# DIY_Keyboard_V1_2.net
KiCad netlist of a schematic drawn in EAGLE
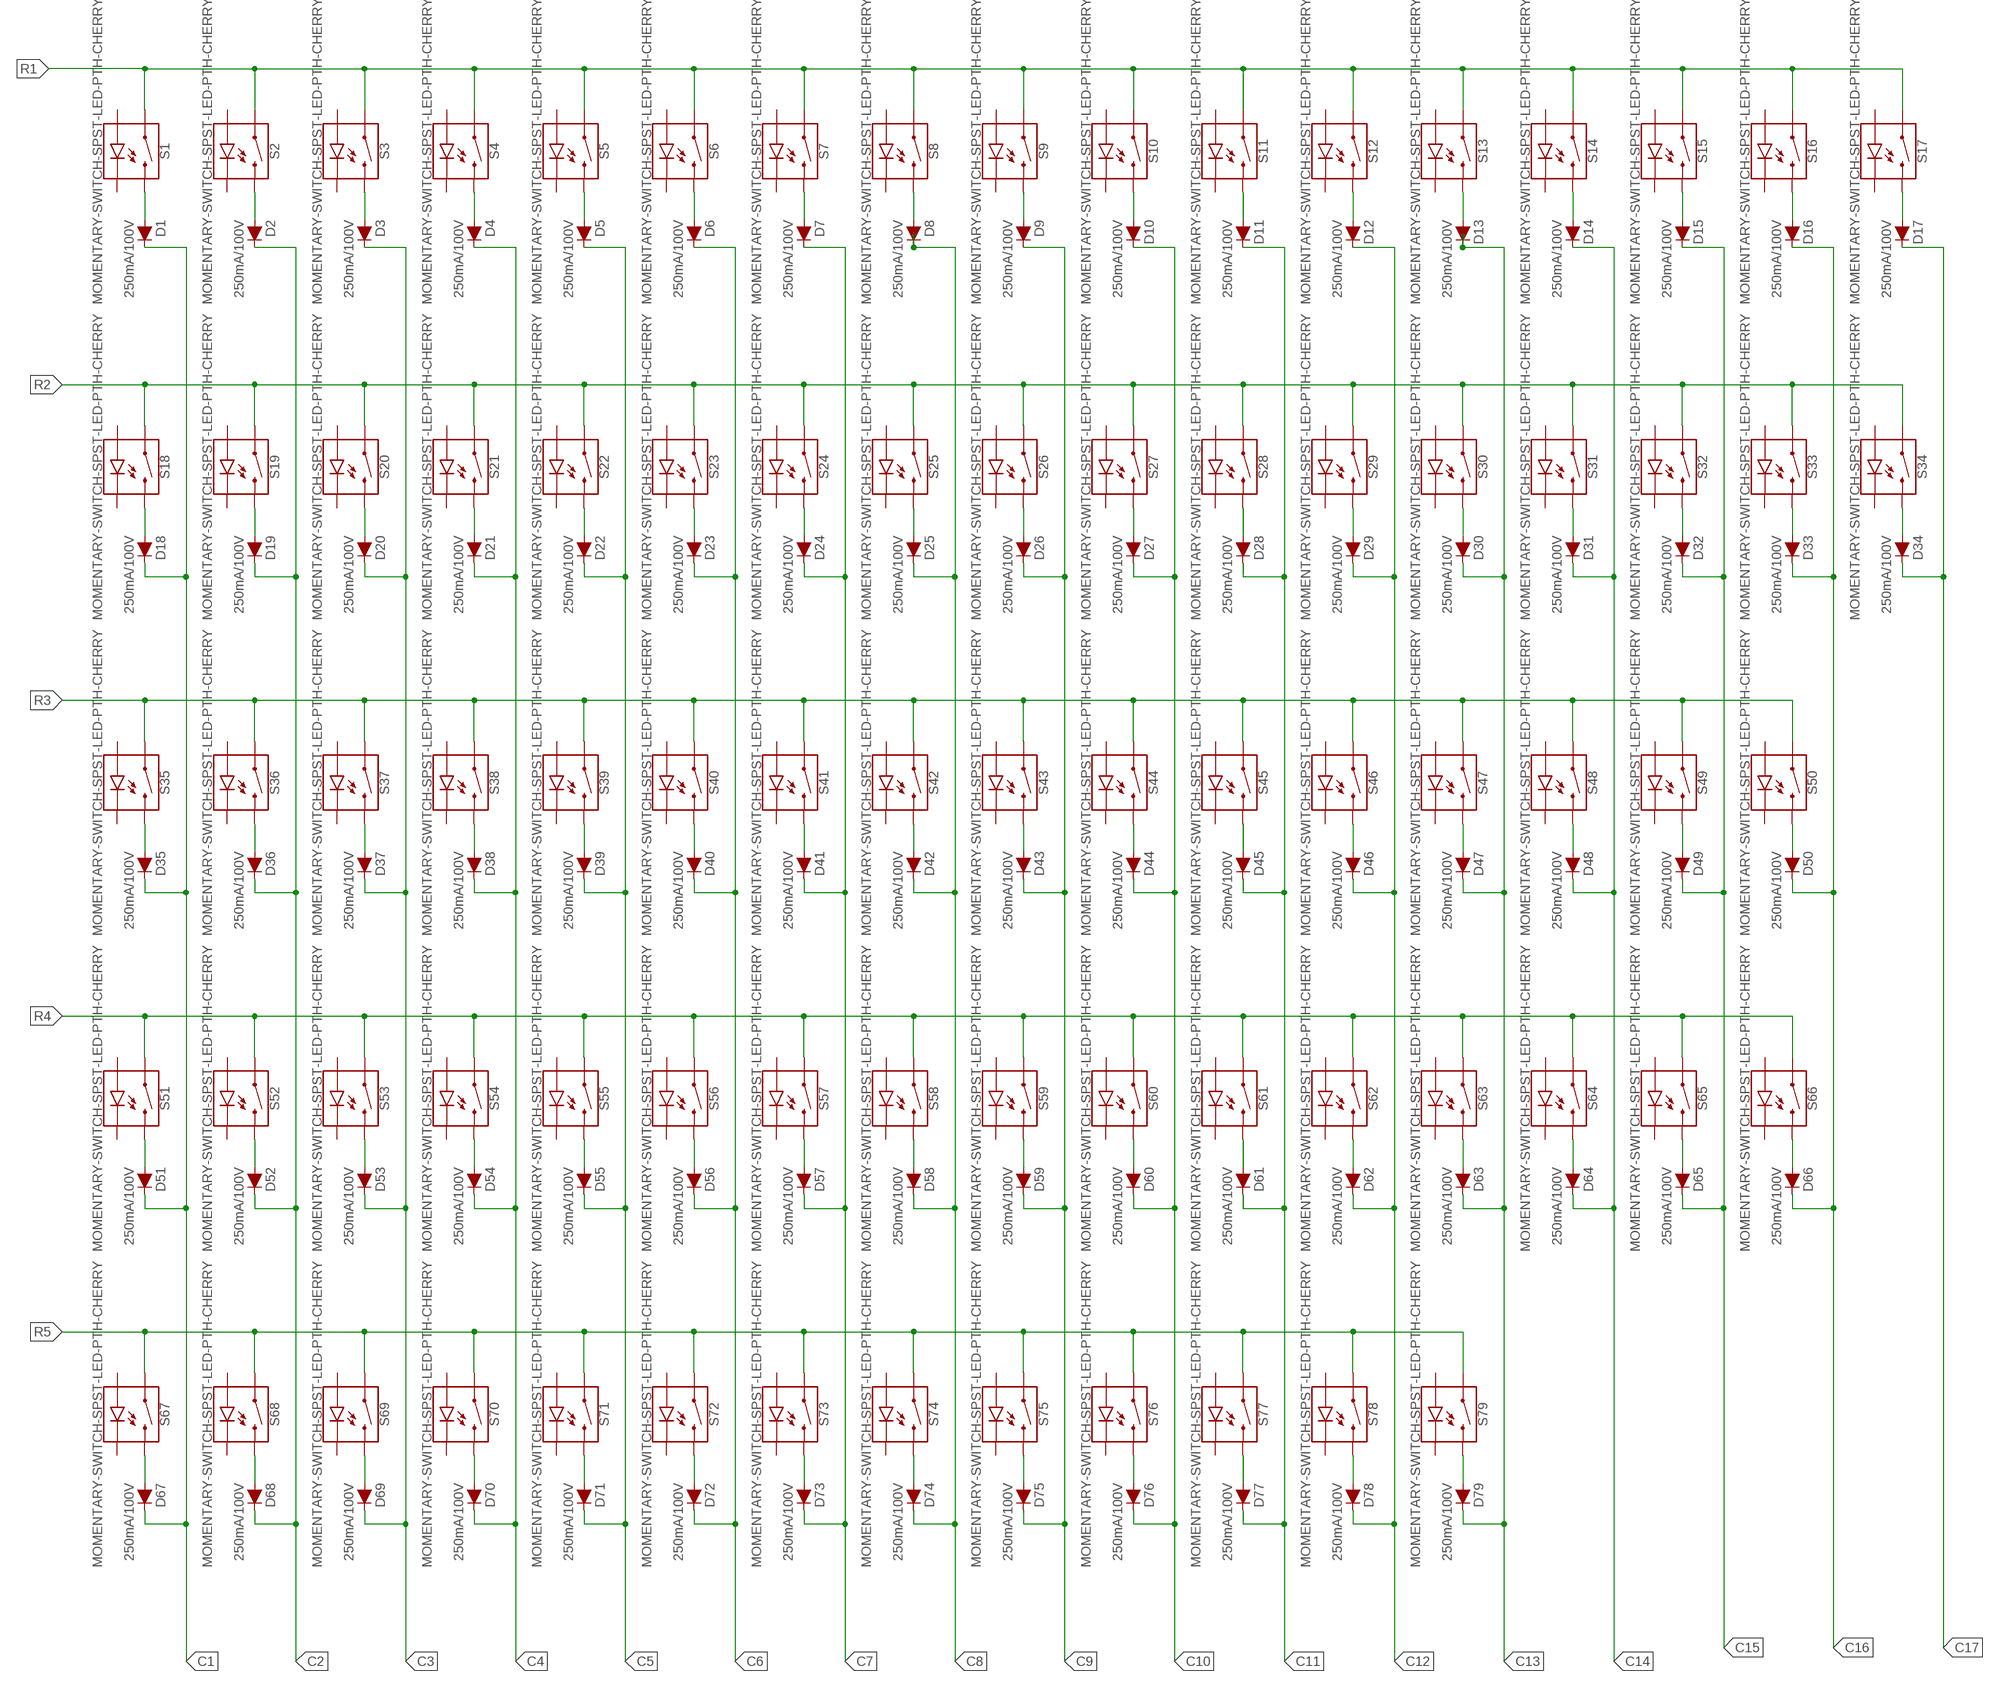
[diagram p0: schematic, sheet 1, part 1 of 2]
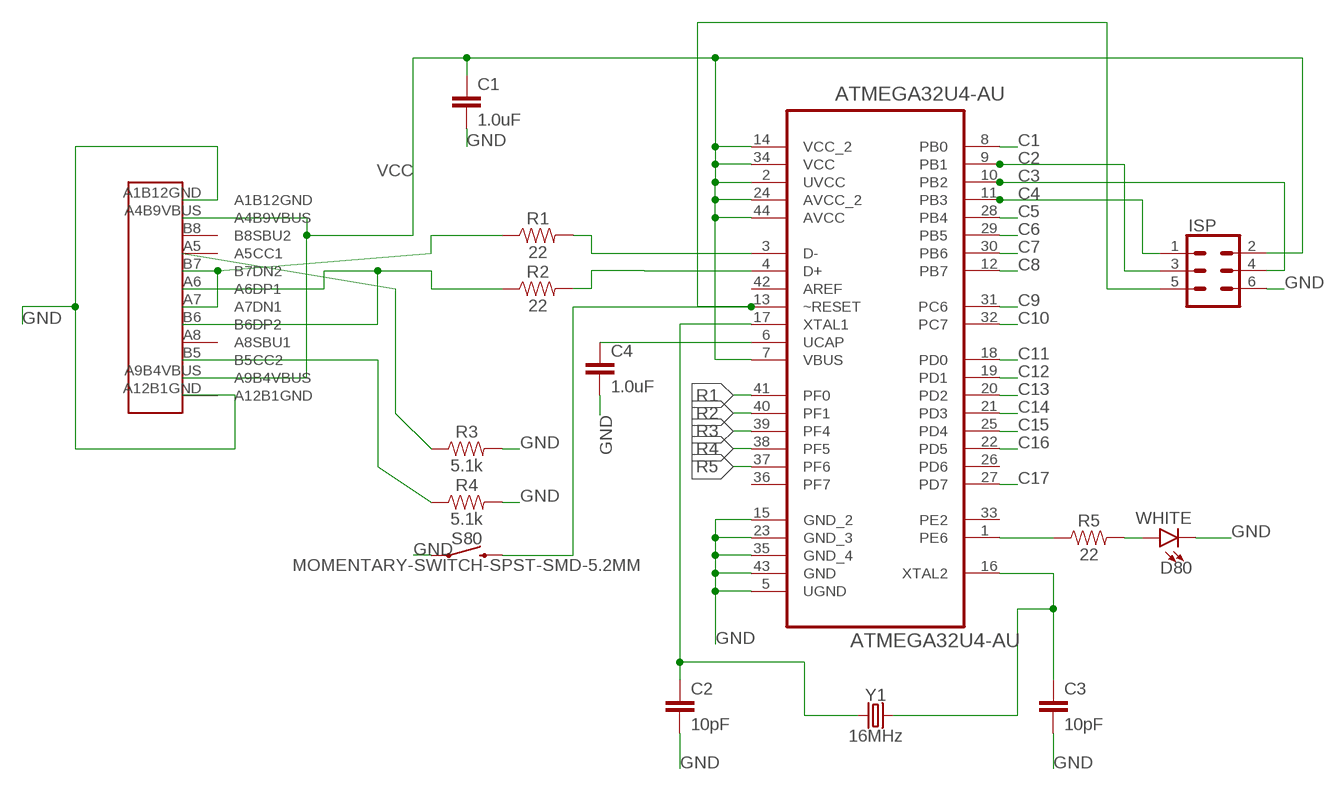
[diagram p1: schematic, sheet 1, part 2 of 2]

(export (version "E")
  (design (tool "Eeschema 10.0.6"))
  (components
    (comp (ref "ATMEGA32U4-AU")
      (value "ATMEGA32U4-AU")
      (footprint "eagle-import:QFP80P1200X1200X120-44N")
      (fields (field (name "MF") "Microchip"))
      (libsource (lib "eagle-import") (part "ATMEGA32U4-AU"))
    )
    (comp (ref "C1")
      (value "1.0uF")
      (footprint "eagle-import:0603")
      (libsource (lib "eagle-import") (part "1.0UF-0603-16V-10%"))
    )
    (comp (ref "C2")
      (value "10pF")
      (footprint "eagle-import:0603")
      (libsource (lib "eagle-import") (part "10PF-0603-50V-5%"))
    )
    (comp (ref "C3")
      (value "10pF")
      (footprint "eagle-import:0603")
      (libsource (lib "eagle-import") (part "10PF-0603-50V-5%"))
    )
    (comp (ref "C4")
      (value "1.0uF")
      (footprint "eagle-import:0603")
      (libsource (lib "eagle-import") (part "1.0UF-0603-16V-10%"))
    )
    (comp (ref "D1")
      (value "250mA/100V")
      (footprint "eagle-import:SOD-323")
      (libsource (lib "eagle-import") (part "DIODE-BAS16J"))
    )
    (comp (ref "D2")
      (value "250mA/100V")
      (footprint "eagle-import:SOD-323")
      (libsource (lib "eagle-import") (part "DIODE-BAS16J"))
    )
    (comp (ref "D3")
      (value "250mA/100V")
      (footprint "eagle-import:SOD-323")
      (libsource (lib "eagle-import") (part "DIODE-BAS16J"))
    )
    (comp (ref "D4")
      (value "250mA/100V")
      (footprint "eagle-import:SOD-323")
      (libsource (lib "eagle-import") (part "DIODE-BAS16J"))
    )
    (comp (ref "D5")
      (value "250mA/100V")
      (footprint "eagle-import:SOD-323")
      (libsource (lib "eagle-import") (part "DIODE-BAS16J"))
    )
    (comp (ref "D6")
      (value "250mA/100V")
      (footprint "eagle-import:SOD-323")
      (libsource (lib "eagle-import") (part "DIODE-BAS16J"))
    )
    (comp (ref "D7")
      (value "250mA/100V")
      (footprint "eagle-import:SOD-323")
      (libsource (lib "eagle-import") (part "DIODE-BAS16J"))
    )
    (comp (ref "D8")
      (value "250mA/100V")
      (footprint "eagle-import:SOD-323")
      (libsource (lib "eagle-import") (part "DIODE-BAS16J"))
    )
    (comp (ref "D9")
      (value "250mA/100V")
      (footprint "eagle-import:SOD-323")
      (libsource (lib "eagle-import") (part "DIODE-BAS16J"))
    )
    (comp (ref "D10")
      (value "250mA/100V")
      (footprint "eagle-import:SOD-323")
      (libsource (lib "eagle-import") (part "DIODE-BAS16J"))
    )
    (comp (ref "D11")
      (value "250mA/100V")
      (footprint "eagle-import:SOD-323")
      (libsource (lib "eagle-import") (part "DIODE-BAS16J"))
    )
    (comp (ref "D12")
      (value "250mA/100V")
      (footprint "eagle-import:SOD-323")
      (libsource (lib "eagle-import") (part "DIODE-BAS16J"))
    )
    (comp (ref "D13")
      (value "250mA/100V")
      (footprint "eagle-import:SOD-323")
      (libsource (lib "eagle-import") (part "DIODE-BAS16J"))
    )
    (comp (ref "D14")
      (value "250mA/100V")
      (footprint "eagle-import:SOD-323")
      (libsource (lib "eagle-import") (part "DIODE-BAS16J"))
    )
    (comp (ref "D15")
      (value "250mA/100V")
      (footprint "eagle-import:SOD-323")
      (libsource (lib "eagle-import") (part "DIODE-BAS16J"))
    )
    (comp (ref "D16")
      (value "250mA/100V")
      (footprint "eagle-import:SOD-323")
      (libsource (lib "eagle-import") (part "DIODE-BAS16J"))
    )
    (comp (ref "D17")
      (value "250mA/100V")
      (footprint "eagle-import:SOD-323")
      (libsource (lib "eagle-import") (part "DIODE-BAS16J"))
    )
    (comp (ref "D18")
      (value "250mA/100V")
      (footprint "eagle-import:SOD-323")
      (libsource (lib "eagle-import") (part "DIODE-BAS16J"))
    )
    (comp (ref "D19")
      (value "250mA/100V")
      (footprint "eagle-import:SOD-323")
      (libsource (lib "eagle-import") (part "DIODE-BAS16J"))
    )
    (comp (ref "D20")
      (value "250mA/100V")
      (footprint "eagle-import:SOD-323")
      (libsource (lib "eagle-import") (part "DIODE-BAS16J"))
    )
    (comp (ref "D21")
      (value "250mA/100V")
      (footprint "eagle-import:SOD-323")
      (libsource (lib "eagle-import") (part "DIODE-BAS16J"))
    )
    (comp (ref "D22")
      (value "250mA/100V")
      (footprint "eagle-import:SOD-323")
      (libsource (lib "eagle-import") (part "DIODE-BAS16J"))
    )
    (comp (ref "D23")
      (value "250mA/100V")
      (footprint "eagle-import:SOD-323")
      (libsource (lib "eagle-import") (part "DIODE-BAS16J"))
    )
    (comp (ref "D24")
      (value "250mA/100V")
      (footprint "eagle-import:SOD-323")
      (libsource (lib "eagle-import") (part "DIODE-BAS16J"))
    )
    (comp (ref "D25")
      (value "250mA/100V")
      (footprint "eagle-import:SOD-323")
      (libsource (lib "eagle-import") (part "DIODE-BAS16J"))
    )
    (comp (ref "D26")
      (value "250mA/100V")
      (footprint "eagle-import:SOD-323")
      (libsource (lib "eagle-import") (part "DIODE-BAS16J"))
    )
    (comp (ref "D27")
      (value "250mA/100V")
      (footprint "eagle-import:SOD-323")
      (libsource (lib "eagle-import") (part "DIODE-BAS16J"))
    )
    (comp (ref "D28")
      (value "250mA/100V")
      (footprint "eagle-import:SOD-323")
      (libsource (lib "eagle-import") (part "DIODE-BAS16J"))
    )
    (comp (ref "D29")
      (value "250mA/100V")
      (footprint "eagle-import:SOD-323")
      (libsource (lib "eagle-import") (part "DIODE-BAS16J"))
    )
    (comp (ref "D30")
      (value "250mA/100V")
      (footprint "eagle-import:SOD-323")
      (libsource (lib "eagle-import") (part "DIODE-BAS16J"))
    )
    (comp (ref "D31")
      (value "250mA/100V")
      (footprint "eagle-import:SOD-323")
      (libsource (lib "eagle-import") (part "DIODE-BAS16J"))
    )
    (comp (ref "D32")
      (value "250mA/100V")
      (footprint "eagle-import:SOD-323")
      (libsource (lib "eagle-import") (part "DIODE-BAS16J"))
    )
    (comp (ref "D33")
      (value "250mA/100V")
      (footprint "eagle-import:SOD-323")
      (libsource (lib "eagle-import") (part "DIODE-BAS16J"))
    )
    (comp (ref "D34")
      (value "250mA/100V")
      (footprint "eagle-import:SOD-323")
      (libsource (lib "eagle-import") (part "DIODE-BAS16J"))
    )
    (comp (ref "D35")
      (value "250mA/100V")
      (footprint "eagle-import:SOD-323")
      (libsource (lib "eagle-import") (part "DIODE-BAS16J"))
    )
    (comp (ref "D36")
      (value "250mA/100V")
      (footprint "eagle-import:SOD-323")
      (libsource (lib "eagle-import") (part "DIODE-BAS16J"))
    )
    (comp (ref "D37")
      (value "250mA/100V")
      (footprint "eagle-import:SOD-323")
      (libsource (lib "eagle-import") (part "DIODE-BAS16J"))
    )
    (comp (ref "D38")
      (value "250mA/100V")
      (footprint "eagle-import:SOD-323")
      (libsource (lib "eagle-import") (part "DIODE-BAS16J"))
    )
    (comp (ref "D39")
      (value "250mA/100V")
      (footprint "eagle-import:SOD-323")
      (libsource (lib "eagle-import") (part "DIODE-BAS16J"))
    )
    (comp (ref "D40")
      (value "250mA/100V")
      (footprint "eagle-import:SOD-323")
      (libsource (lib "eagle-import") (part "DIODE-BAS16J"))
    )
    (comp (ref "D41")
      (value "250mA/100V")
      (footprint "eagle-import:SOD-323")
      (libsource (lib "eagle-import") (part "DIODE-BAS16J"))
    )
    (comp (ref "D42")
      (value "250mA/100V")
      (footprint "eagle-import:SOD-323")
      (libsource (lib "eagle-import") (part "DIODE-BAS16J"))
    )
    (comp (ref "D43")
      (value "250mA/100V")
      (footprint "eagle-import:SOD-323")
      (libsource (lib "eagle-import") (part "DIODE-BAS16J"))
    )
    (comp (ref "D44")
      (value "250mA/100V")
      (footprint "eagle-import:SOD-323")
      (libsource (lib "eagle-import") (part "DIODE-BAS16J"))
    )
    (comp (ref "D45")
      (value "250mA/100V")
      (footprint "eagle-import:SOD-323")
      (libsource (lib "eagle-import") (part "DIODE-BAS16J"))
    )
    (comp (ref "D46")
      (value "250mA/100V")
      (footprint "eagle-import:SOD-323")
      (libsource (lib "eagle-import") (part "DIODE-BAS16J"))
    )
    (comp (ref "D47")
      (value "250mA/100V")
      (footprint "eagle-import:SOD-323")
      (libsource (lib "eagle-import") (part "DIODE-BAS16J"))
    )
    (comp (ref "D48")
      (value "250mA/100V")
      (footprint "eagle-import:SOD-323")
      (libsource (lib "eagle-import") (part "DIODE-BAS16J"))
    )
    (comp (ref "D49")
      (value "250mA/100V")
      (footprint "eagle-import:SOD-323")
      (libsource (lib "eagle-import") (part "DIODE-BAS16J"))
    )
    (comp (ref "D50")
      (value "250mA/100V")
      (footprint "eagle-import:SOD-323")
      (libsource (lib "eagle-import") (part "DIODE-BAS16J"))
    )
    (comp (ref "D51")
      (value "250mA/100V")
      (footprint "eagle-import:SOD-323")
      (libsource (lib "eagle-import") (part "DIODE-BAS16J"))
    )
    (comp (ref "D52")
      (value "250mA/100V")
      (footprint "eagle-import:SOD-323")
      (libsource (lib "eagle-import") (part "DIODE-BAS16J"))
    )
    (comp (ref "D53")
      (value "250mA/100V")
      (footprint "eagle-import:SOD-323")
      (libsource (lib "eagle-import") (part "DIODE-BAS16J"))
    )
    (comp (ref "D54")
      (value "250mA/100V")
      (footprint "eagle-import:SOD-323")
      (libsource (lib "eagle-import") (part "DIODE-BAS16J"))
    )
    (comp (ref "D55")
      (value "250mA/100V")
      (footprint "eagle-import:SOD-323")
      (libsource (lib "eagle-import") (part "DIODE-BAS16J"))
    )
    (comp (ref "D56")
      (value "250mA/100V")
      (footprint "eagle-import:SOD-323")
      (libsource (lib "eagle-import") (part "DIODE-BAS16J"))
    )
    (comp (ref "D57")
      (value "250mA/100V")
      (footprint "eagle-import:SOD-323")
      (libsource (lib "eagle-import") (part "DIODE-BAS16J"))
    )
    (comp (ref "D58")
      (value "250mA/100V")
      (footprint "eagle-import:SOD-323")
      (libsource (lib "eagle-import") (part "DIODE-BAS16J"))
    )
    (comp (ref "D59")
      (value "250mA/100V")
      (footprint "eagle-import:SOD-323")
      (libsource (lib "eagle-import") (part "DIODE-BAS16J"))
    )
    (comp (ref "D60")
      (value "250mA/100V")
      (footprint "eagle-import:SOD-323")
      (libsource (lib "eagle-import") (part "DIODE-BAS16J"))
    )
    (comp (ref "D61")
      (value "250mA/100V")
      (footprint "eagle-import:SOD-323")
      (libsource (lib "eagle-import") (part "DIODE-BAS16J"))
    )
    (comp (ref "D62")
      (value "250mA/100V")
      (footprint "eagle-import:SOD-323")
      (libsource (lib "eagle-import") (part "DIODE-BAS16J"))
    )
    (comp (ref "D63")
      (value "250mA/100V")
      (footprint "eagle-import:SOD-323")
      (libsource (lib "eagle-import") (part "DIODE-BAS16J"))
    )
    (comp (ref "D64")
      (value "250mA/100V")
      (footprint "eagle-import:SOD-323")
      (libsource (lib "eagle-import") (part "DIODE-BAS16J"))
    )
    (comp (ref "D65")
      (value "250mA/100V")
      (footprint "eagle-import:SOD-323")
      (libsource (lib "eagle-import") (part "DIODE-BAS16J"))
    )
    (comp (ref "D66")
      (value "250mA/100V")
      (footprint "eagle-import:SOD-323")
      (libsource (lib "eagle-import") (part "DIODE-BAS16J"))
    )
    (comp (ref "D67")
      (value "250mA/100V")
      (footprint "eagle-import:SOD-323")
      (libsource (lib "eagle-import") (part "DIODE-BAS16J"))
    )
    (comp (ref "D68")
      (value "250mA/100V")
      (footprint "eagle-import:SOD-323")
      (libsource (lib "eagle-import") (part "DIODE-BAS16J"))
    )
    (comp (ref "D69")
      (value "250mA/100V")
      (footprint "eagle-import:SOD-323")
      (libsource (lib "eagle-import") (part "DIODE-BAS16J"))
    )
    (comp (ref "D70")
      (value "250mA/100V")
      (footprint "eagle-import:SOD-323")
      (libsource (lib "eagle-import") (part "DIODE-BAS16J"))
    )
    (comp (ref "D71")
      (value "250mA/100V")
      (footprint "eagle-import:SOD-323")
      (libsource (lib "eagle-import") (part "DIODE-BAS16J"))
    )
    (comp (ref "D72")
      (value "250mA/100V")
      (footprint "eagle-import:SOD-323")
      (libsource (lib "eagle-import") (part "DIODE-BAS16J"))
    )
    (comp (ref "D73")
      (value "250mA/100V")
      (footprint "eagle-import:SOD-323")
      (libsource (lib "eagle-import") (part "DIODE-BAS16J"))
    )
    (comp (ref "D74")
      (value "250mA/100V")
      (footprint "eagle-import:SOD-323")
      (libsource (lib "eagle-import") (part "DIODE-BAS16J"))
    )
    (comp (ref "D75")
      (value "250mA/100V")
      (footprint "eagle-import:SOD-323")
      (libsource (lib "eagle-import") (part "DIODE-BAS16J"))
    )
    (comp (ref "D76")
      (value "250mA/100V")
      (footprint "eagle-import:SOD-323")
      (libsource (lib "eagle-import") (part "DIODE-BAS16J"))
    )
    (comp (ref "D77")
      (value "250mA/100V")
      (footprint "eagle-import:SOD-323")
      (libsource (lib "eagle-import") (part "DIODE-BAS16J"))
    )
    (comp (ref "D78")
      (value "250mA/100V")
      (footprint "eagle-import:SOD-323")
      (libsource (lib "eagle-import") (part "DIODE-BAS16J"))
    )
    (comp (ref "D79")
      (value "250mA/100V")
      (footprint "eagle-import:SOD-323")
      (libsource (lib "eagle-import") (part "DIODE-BAS16J"))
    )
    (comp (ref "D80")
      (value "WHITE")
      (footprint "eagle-import:LED-0603")
      (libsource (lib "eagle-import") (part "LED-WHITE0603"))
    )
    (comp (ref "ISP")
      (value "CONN_03X2FEMALE")
      (footprint "eagle-import:2X3")
      (libsource (lib "eagle-import") (part "CONN_03X2FEMALE"))
    )
    (comp (ref "R1")
      (value "22")
      (footprint "eagle-import:0603")
      (libsource (lib "eagle-import") (part "22OHM-0603-1/10W-1%"))
    )
    (comp (ref "R2")
      (value "22")
      (footprint "eagle-import:0603")
      (libsource (lib "eagle-import") (part "22OHM-0603-1/10W-1%"))
    )
    (comp (ref "R3")
      (value "5.1k")
      (footprint "eagle-import:0603")
      (libsource (lib "eagle-import") (part "56KOHM"))
    )
    (comp (ref "R4")
      (value "5.1k")
      (footprint "eagle-import:0603")
      (libsource (lib "eagle-import") (part "56KOHM"))
    )
    (comp (ref "R5")
      (value "22")
      (footprint "eagle-import:0603")
      (libsource (lib "eagle-import") (part "22OHM-0603-1/10W-1%"))
    )
    (comp (ref "S1")
      (value "MOMENTARY-SWITCH-SPST-LED-PTH-CHERRY")
      (footprint "eagle-import:CHERRY-MX-LED")
      (libsource (lib "eagle-import") (part "MOMENTARY-SWITCH-SPST-LED-PTH-CHERRY"))
    )
    (comp (ref "S2")
      (value "MOMENTARY-SWITCH-SPST-LED-PTH-CHERRY")
      (footprint "eagle-import:CHERRY-MX-LED")
      (libsource (lib "eagle-import") (part "MOMENTARY-SWITCH-SPST-LED-PTH-CHERRY"))
    )
    (comp (ref "S3")
      (value "MOMENTARY-SWITCH-SPST-LED-PTH-CHERRY")
      (footprint "eagle-import:CHERRY-MX-LED")
      (libsource (lib "eagle-import") (part "MOMENTARY-SWITCH-SPST-LED-PTH-CHERRY"))
    )
    (comp (ref "S4")
      (value "MOMENTARY-SWITCH-SPST-LED-PTH-CHERRY")
      (footprint "eagle-import:CHERRY-MX-LED")
      (libsource (lib "eagle-import") (part "MOMENTARY-SWITCH-SPST-LED-PTH-CHERRY"))
    )
    (comp (ref "S5")
      (value "MOMENTARY-SWITCH-SPST-LED-PTH-CHERRY")
      (footprint "eagle-import:CHERRY-MX-LED")
      (libsource (lib "eagle-import") (part "MOMENTARY-SWITCH-SPST-LED-PTH-CHERRY"))
    )
    (comp (ref "S6")
      (value "MOMENTARY-SWITCH-SPST-LED-PTH-CHERRY")
      (footprint "eagle-import:CHERRY-MX-LED")
      (libsource (lib "eagle-import") (part "MOMENTARY-SWITCH-SPST-LED-PTH-CHERRY"))
    )
    (comp (ref "S7")
      (value "MOMENTARY-SWITCH-SPST-LED-PTH-CHERRY")
      (footprint "eagle-import:CHERRY-MX-LED")
      (libsource (lib "eagle-import") (part "MOMENTARY-SWITCH-SPST-LED-PTH-CHERRY"))
    )
    (comp (ref "S8")
      (value "MOMENTARY-SWITCH-SPST-LED-PTH-CHERRY")
      (footprint "eagle-import:CHERRY-MX-LED")
      (libsource (lib "eagle-import") (part "MOMENTARY-SWITCH-SPST-LED-PTH-CHERRY"))
    )
    (comp (ref "S9")
      (value "MOMENTARY-SWITCH-SPST-LED-PTH-CHERRY")
      (footprint "eagle-import:CHERRY-MX-LED")
      (libsource (lib "eagle-import") (part "MOMENTARY-SWITCH-SPST-LED-PTH-CHERRY"))
    )
    (comp (ref "S10")
      (value "MOMENTARY-SWITCH-SPST-LED-PTH-CHERRY")
      (footprint "eagle-import:CHERRY-MX-LED")
      (libsource (lib "eagle-import") (part "MOMENTARY-SWITCH-SPST-LED-PTH-CHERRY"))
    )
    (comp (ref "S11")
      (value "MOMENTARY-SWITCH-SPST-LED-PTH-CHERRY")
      (footprint "eagle-import:CHERRY-MX-LED")
      (libsource (lib "eagle-import") (part "MOMENTARY-SWITCH-SPST-LED-PTH-CHERRY"))
    )
    (comp (ref "S12")
      (value "MOMENTARY-SWITCH-SPST-LED-PTH-CHERRY")
      (footprint "eagle-import:CHERRY-MX-LED")
      (libsource (lib "eagle-import") (part "MOMENTARY-SWITCH-SPST-LED-PTH-CHERRY"))
    )
    (comp (ref "S13")
      (value "MOMENTARY-SWITCH-SPST-LED-PTH-CHERRY")
      (footprint "eagle-import:CHERRY-MX-LED")
      (libsource (lib "eagle-import") (part "MOMENTARY-SWITCH-SPST-LED-PTH-CHERRY"))
    )
    (comp (ref "S14")
      (value "MOMENTARY-SWITCH-SPST-LED-PTH-CHERRY")
      (footprint "eagle-import:CHERRY-MX-LED")
      (libsource (lib "eagle-import") (part "MOMENTARY-SWITCH-SPST-LED-PTH-CHERRY"))
    )
    (comp (ref "S15")
      (value "MOMENTARY-SWITCH-SPST-LED-PTH-CHERRY")
      (footprint "eagle-import:CHERRY-MX-LED")
      (libsource (lib "eagle-import") (part "MOMENTARY-SWITCH-SPST-LED-PTH-CHERRY"))
    )
    (comp (ref "S16")
      (value "MOMENTARY-SWITCH-SPST-LED-PTH-CHERRY")
      (footprint "eagle-import:CHERRY-MX-LED")
      (libsource (lib "eagle-import") (part "MOMENTARY-SWITCH-SPST-LED-PTH-CHERRY"))
    )
    (comp (ref "S17")
      (value "MOMENTARY-SWITCH-SPST-LED-PTH-CHERRY")
      (footprint "eagle-import:CHERRY-MX-LED")
      (libsource (lib "eagle-import") (part "MOMENTARY-SWITCH-SPST-LED-PTH-CHERRY"))
    )
    (comp (ref "S18")
      (value "MOMENTARY-SWITCH-SPST-LED-PTH-CHERRY")
      (footprint "eagle-import:CHERRY-MX-LED")
      (libsource (lib "eagle-import") (part "MOMENTARY-SWITCH-SPST-LED-PTH-CHERRY"))
    )
    (comp (ref "S19")
      (value "MOMENTARY-SWITCH-SPST-LED-PTH-CHERRY")
      (footprint "eagle-import:CHERRY-MX-LED")
      (libsource (lib "eagle-import") (part "MOMENTARY-SWITCH-SPST-LED-PTH-CHERRY"))
    )
    (comp (ref "S20")
      (value "MOMENTARY-SWITCH-SPST-LED-PTH-CHERRY")
      (footprint "eagle-import:CHERRY-MX-LED")
      (libsource (lib "eagle-import") (part "MOMENTARY-SWITCH-SPST-LED-PTH-CHERRY"))
    )
    (comp (ref "S21")
      (value "MOMENTARY-SWITCH-SPST-LED-PTH-CHERRY")
      (footprint "eagle-import:CHERRY-MX-LED")
      (libsource (lib "eagle-import") (part "MOMENTARY-SWITCH-SPST-LED-PTH-CHERRY"))
    )
    (comp (ref "S22")
      (value "MOMENTARY-SWITCH-SPST-LED-PTH-CHERRY")
      (footprint "eagle-import:CHERRY-MX-LED")
      (libsource (lib "eagle-import") (part "MOMENTARY-SWITCH-SPST-LED-PTH-CHERRY"))
    )
    (comp (ref "S23")
      (value "MOMENTARY-SWITCH-SPST-LED-PTH-CHERRY")
      (footprint "eagle-import:CHERRY-MX-LED")
      (libsource (lib "eagle-import") (part "MOMENTARY-SWITCH-SPST-LED-PTH-CHERRY"))
    )
    (comp (ref "S24")
      (value "MOMENTARY-SWITCH-SPST-LED-PTH-CHERRY")
      (footprint "eagle-import:CHERRY-MX-LED")
      (libsource (lib "eagle-import") (part "MOMENTARY-SWITCH-SPST-LED-PTH-CHERRY"))
    )
    (comp (ref "S25")
      (value "MOMENTARY-SWITCH-SPST-LED-PTH-CHERRY")
      (footprint "eagle-import:CHERRY-MX-LED")
      (libsource (lib "eagle-import") (part "MOMENTARY-SWITCH-SPST-LED-PTH-CHERRY"))
    )
    (comp (ref "S26")
      (value "MOMENTARY-SWITCH-SPST-LED-PTH-CHERRY")
      (footprint "eagle-import:CHERRY-MX-LED")
      (libsource (lib "eagle-import") (part "MOMENTARY-SWITCH-SPST-LED-PTH-CHERRY"))
    )
    (comp (ref "S27")
      (value "MOMENTARY-SWITCH-SPST-LED-PTH-CHERRY")
      (footprint "eagle-import:CHERRY-MX-LED")
      (libsource (lib "eagle-import") (part "MOMENTARY-SWITCH-SPST-LED-PTH-CHERRY"))
    )
    (comp (ref "S28")
      (value "MOMENTARY-SWITCH-SPST-LED-PTH-CHERRY")
      (footprint "eagle-import:CHERRY-MX-LED")
      (libsource (lib "eagle-import") (part "MOMENTARY-SWITCH-SPST-LED-PTH-CHERRY"))
    )
    (comp (ref "S29")
      (value "MOMENTARY-SWITCH-SPST-LED-PTH-CHERRY")
      (footprint "eagle-import:CHERRY-MX-LED")
      (libsource (lib "eagle-import") (part "MOMENTARY-SWITCH-SPST-LED-PTH-CHERRY"))
    )
    (comp (ref "S30")
      (value "MOMENTARY-SWITCH-SPST-LED-PTH-CHERRY")
      (footprint "eagle-import:CHERRY-MX-LED")
      (libsource (lib "eagle-import") (part "MOMENTARY-SWITCH-SPST-LED-PTH-CHERRY"))
    )
    (comp (ref "S31")
      (value "MOMENTARY-SWITCH-SPST-LED-PTH-CHERRY")
      (footprint "eagle-import:CHERRY-MX-LED")
      (libsource (lib "eagle-import") (part "MOMENTARY-SWITCH-SPST-LED-PTH-CHERRY"))
    )
    (comp (ref "S32")
      (value "MOMENTARY-SWITCH-SPST-LED-PTH-CHERRY")
      (footprint "eagle-import:CHERRY-MX-LED")
      (libsource (lib "eagle-import") (part "MOMENTARY-SWITCH-SPST-LED-PTH-CHERRY"))
    )
    (comp (ref "S33")
      (value "MOMENTARY-SWITCH-SPST-LED-PTH-CHERRY")
      (footprint "eagle-import:CHERRY-MX-LED")
      (libsource (lib "eagle-import") (part "MOMENTARY-SWITCH-SPST-LED-PTH-CHERRY"))
    )
    (comp (ref "S34")
      (value "MOMENTARY-SWITCH-SPST-LED-PTH-CHERRY")
      (footprint "eagle-import:CHERRY-MX-LED")
      (libsource (lib "eagle-import") (part "MOMENTARY-SWITCH-SPST-LED-PTH-CHERRY"))
    )
    (comp (ref "S35")
      (value "MOMENTARY-SWITCH-SPST-LED-PTH-CHERRY")
      (footprint "eagle-import:CHERRY-MX-LED")
      (libsource (lib "eagle-import") (part "MOMENTARY-SWITCH-SPST-LED-PTH-CHERRY"))
    )
    (comp (ref "S36")
      (value "MOMENTARY-SWITCH-SPST-LED-PTH-CHERRY")
      (footprint "eagle-import:CHERRY-MX-LED")
      (libsource (lib "eagle-import") (part "MOMENTARY-SWITCH-SPST-LED-PTH-CHERRY"))
    )
    (comp (ref "S37")
      (value "MOMENTARY-SWITCH-SPST-LED-PTH-CHERRY")
      (footprint "eagle-import:CHERRY-MX-LED")
      (libsource (lib "eagle-import") (part "MOMENTARY-SWITCH-SPST-LED-PTH-CHERRY"))
    )
    (comp (ref "S38")
      (value "MOMENTARY-SWITCH-SPST-LED-PTH-CHERRY")
      (footprint "eagle-import:CHERRY-MX-LED")
      (libsource (lib "eagle-import") (part "MOMENTARY-SWITCH-SPST-LED-PTH-CHERRY"))
    )
    (comp (ref "S39")
      (value "MOMENTARY-SWITCH-SPST-LED-PTH-CHERRY")
      (footprint "eagle-import:CHERRY-MX-LED")
      (libsource (lib "eagle-import") (part "MOMENTARY-SWITCH-SPST-LED-PTH-CHERRY"))
    )
    (comp (ref "S40")
      (value "MOMENTARY-SWITCH-SPST-LED-PTH-CHERRY")
      (footprint "eagle-import:CHERRY-MX-LED")
      (libsource (lib "eagle-import") (part "MOMENTARY-SWITCH-SPST-LED-PTH-CHERRY"))
    )
    (comp (ref "S41")
      (value "MOMENTARY-SWITCH-SPST-LED-PTH-CHERRY")
      (footprint "eagle-import:CHERRY-MX-LED")
      (libsource (lib "eagle-import") (part "MOMENTARY-SWITCH-SPST-LED-PTH-CHERRY"))
    )
    (comp (ref "S42")
      (value "MOMENTARY-SWITCH-SPST-LED-PTH-CHERRY")
      (footprint "eagle-import:CHERRY-MX-LED")
      (libsource (lib "eagle-import") (part "MOMENTARY-SWITCH-SPST-LED-PTH-CHERRY"))
    )
    (comp (ref "S43")
      (value "MOMENTARY-SWITCH-SPST-LED-PTH-CHERRY")
      (footprint "eagle-import:CHERRY-MX-LED")
      (libsource (lib "eagle-import") (part "MOMENTARY-SWITCH-SPST-LED-PTH-CHERRY"))
    )
    (comp (ref "S44")
      (value "MOMENTARY-SWITCH-SPST-LED-PTH-CHERRY")
      (footprint "eagle-import:CHERRY-MX-LED")
      (libsource (lib "eagle-import") (part "MOMENTARY-SWITCH-SPST-LED-PTH-CHERRY"))
    )
    (comp (ref "S45")
      (value "MOMENTARY-SWITCH-SPST-LED-PTH-CHERRY")
      (footprint "eagle-import:CHERRY-MX-LED")
      (libsource (lib "eagle-import") (part "MOMENTARY-SWITCH-SPST-LED-PTH-CHERRY"))
    )
    (comp (ref "S46")
      (value "MOMENTARY-SWITCH-SPST-LED-PTH-CHERRY")
      (footprint "eagle-import:CHERRY-MX-LED")
      (libsource (lib "eagle-import") (part "MOMENTARY-SWITCH-SPST-LED-PTH-CHERRY"))
    )
    (comp (ref "S47")
      (value "MOMENTARY-SWITCH-SPST-LED-PTH-CHERRY")
      (footprint "eagle-import:CHERRY-MX-LED")
      (libsource (lib "eagle-import") (part "MOMENTARY-SWITCH-SPST-LED-PTH-CHERRY"))
    )
    (comp (ref "S48")
      (value "MOMENTARY-SWITCH-SPST-LED-PTH-CHERRY")
      (footprint "eagle-import:CHERRY-MX-LED")
      (libsource (lib "eagle-import") (part "MOMENTARY-SWITCH-SPST-LED-PTH-CHERRY"))
    )
    (comp (ref "S49")
      (value "MOMENTARY-SWITCH-SPST-LED-PTH-CHERRY")
      (footprint "eagle-import:CHERRY-MX-LED")
      (libsource (lib "eagle-import") (part "MOMENTARY-SWITCH-SPST-LED-PTH-CHERRY"))
    )
    (comp (ref "S50")
      (value "MOMENTARY-SWITCH-SPST-LED-PTH-CHERRY")
      (footprint "eagle-import:CHERRY-MX-LED")
      (libsource (lib "eagle-import") (part "MOMENTARY-SWITCH-SPST-LED-PTH-CHERRY"))
    )
    (comp (ref "S51")
      (value "MOMENTARY-SWITCH-SPST-LED-PTH-CHERRY")
      (footprint "eagle-import:CHERRY-MX-LED")
      (libsource (lib "eagle-import") (part "MOMENTARY-SWITCH-SPST-LED-PTH-CHERRY"))
    )
    (comp (ref "S52")
      (value "MOMENTARY-SWITCH-SPST-LED-PTH-CHERRY")
      (footprint "eagle-import:CHERRY-MX-LED")
      (libsource (lib "eagle-import") (part "MOMENTARY-SWITCH-SPST-LED-PTH-CHERRY"))
    )
    (comp (ref "S53")
      (value "MOMENTARY-SWITCH-SPST-LED-PTH-CHERRY")
      (footprint "eagle-import:CHERRY-MX-LED")
      (libsource (lib "eagle-import") (part "MOMENTARY-SWITCH-SPST-LED-PTH-CHERRY"))
    )
    (comp (ref "S54")
      (value "MOMENTARY-SWITCH-SPST-LED-PTH-CHERRY")
      (footprint "eagle-import:CHERRY-MX-LED")
      (libsource (lib "eagle-import") (part "MOMENTARY-SWITCH-SPST-LED-PTH-CHERRY"))
    )
    (comp (ref "S55")
      (value "MOMENTARY-SWITCH-SPST-LED-PTH-CHERRY")
      (footprint "eagle-import:CHERRY-MX-LED")
      (libsource (lib "eagle-import") (part "MOMENTARY-SWITCH-SPST-LED-PTH-CHERRY"))
    )
    (comp (ref "S56")
      (value "MOMENTARY-SWITCH-SPST-LED-PTH-CHERRY")
      (footprint "eagle-import:CHERRY-MX-LED")
      (libsource (lib "eagle-import") (part "MOMENTARY-SWITCH-SPST-LED-PTH-CHERRY"))
    )
    (comp (ref "S57")
      (value "MOMENTARY-SWITCH-SPST-LED-PTH-CHERRY")
      (footprint "eagle-import:CHERRY-MX-LED")
      (libsource (lib "eagle-import") (part "MOMENTARY-SWITCH-SPST-LED-PTH-CHERRY"))
    )
    (comp (ref "S58")
      (value "MOMENTARY-SWITCH-SPST-LED-PTH-CHERRY")
      (footprint "eagle-import:CHERRY-MX-LED")
      (libsource (lib "eagle-import") (part "MOMENTARY-SWITCH-SPST-LED-PTH-CHERRY"))
    )
    (comp (ref "S59")
      (value "MOMENTARY-SWITCH-SPST-LED-PTH-CHERRY")
      (footprint "eagle-import:CHERRY-MX-LED")
      (libsource (lib "eagle-import") (part "MOMENTARY-SWITCH-SPST-LED-PTH-CHERRY"))
    )
    (comp (ref "S60")
      (value "MOMENTARY-SWITCH-SPST-LED-PTH-CHERRY")
      (footprint "eagle-import:CHERRY-MX-LED")
      (libsource (lib "eagle-import") (part "MOMENTARY-SWITCH-SPST-LED-PTH-CHERRY"))
    )
    (comp (ref "S61")
      (value "MOMENTARY-SWITCH-SPST-LED-PTH-CHERRY")
      (footprint "eagle-import:CHERRY-MX-LED")
      (libsource (lib "eagle-import") (part "MOMENTARY-SWITCH-SPST-LED-PTH-CHERRY"))
    )
    (comp (ref "S62")
      (value "MOMENTARY-SWITCH-SPST-LED-PTH-CHERRY")
      (footprint "eagle-import:CHERRY-MX-LED")
      (libsource (lib "eagle-import") (part "MOMENTARY-SWITCH-SPST-LED-PTH-CHERRY"))
    )
    (comp (ref "S63")
      (value "MOMENTARY-SWITCH-SPST-LED-PTH-CHERRY")
      (footprint "eagle-import:CHERRY-MX-LED")
      (libsource (lib "eagle-import") (part "MOMENTARY-SWITCH-SPST-LED-PTH-CHERRY"))
    )
    (comp (ref "S64")
      (value "MOMENTARY-SWITCH-SPST-LED-PTH-CHERRY")
      (footprint "eagle-import:CHERRY-MX-LED")
      (libsource (lib "eagle-import") (part "MOMENTARY-SWITCH-SPST-LED-PTH-CHERRY"))
    )
    (comp (ref "S65")
      (value "MOMENTARY-SWITCH-SPST-LED-PTH-CHERRY")
      (footprint "eagle-import:CHERRY-MX-LED")
      (libsource (lib "eagle-import") (part "MOMENTARY-SWITCH-SPST-LED-PTH-CHERRY"))
    )
    (comp (ref "S66")
      (value "MOMENTARY-SWITCH-SPST-LED-PTH-CHERRY")
      (footprint "eagle-import:CHERRY-MX-LED")
      (libsource (lib "eagle-import") (part "MOMENTARY-SWITCH-SPST-LED-PTH-CHERRY"))
    )
    (comp (ref "S67")
      (value "MOMENTARY-SWITCH-SPST-LED-PTH-CHERRY")
      (footprint "eagle-import:CHERRY-MX-LED")
      (libsource (lib "eagle-import") (part "MOMENTARY-SWITCH-SPST-LED-PTH-CHERRY"))
    )
    (comp (ref "S68")
      (value "MOMENTARY-SWITCH-SPST-LED-PTH-CHERRY")
      (footprint "eagle-import:CHERRY-MX-LED")
      (libsource (lib "eagle-import") (part "MOMENTARY-SWITCH-SPST-LED-PTH-CHERRY"))
    )
    (comp (ref "S69")
      (value "MOMENTARY-SWITCH-SPST-LED-PTH-CHERRY")
      (footprint "eagle-import:CHERRY-MX-LED")
      (libsource (lib "eagle-import") (part "MOMENTARY-SWITCH-SPST-LED-PTH-CHERRY"))
    )
    (comp (ref "S70")
      (value "MOMENTARY-SWITCH-SPST-LED-PTH-CHERRY")
      (footprint "eagle-import:CHERRY-MX-LED")
      (libsource (lib "eagle-import") (part "MOMENTARY-SWITCH-SPST-LED-PTH-CHERRY"))
    )
    (comp (ref "S71")
      (value "MOMENTARY-SWITCH-SPST-LED-PTH-CHERRY")
      (footprint "eagle-import:CHERRY-MX-LED")
      (libsource (lib "eagle-import") (part "MOMENTARY-SWITCH-SPST-LED-PTH-CHERRY"))
    )
    (comp (ref "S72")
      (value "MOMENTARY-SWITCH-SPST-LED-PTH-CHERRY")
      (footprint "eagle-import:CHERRY-MX-LED")
      (libsource (lib "eagle-import") (part "MOMENTARY-SWITCH-SPST-LED-PTH-CHERRY"))
    )
    (comp (ref "S73")
      (value "MOMENTARY-SWITCH-SPST-LED-PTH-CHERRY")
      (footprint "eagle-import:CHERRY-MX-LED")
      (libsource (lib "eagle-import") (part "MOMENTARY-SWITCH-SPST-LED-PTH-CHERRY"))
    )
    (comp (ref "S74")
      (value "MOMENTARY-SWITCH-SPST-LED-PTH-CHERRY")
      (footprint "eagle-import:CHERRY-MX-LED")
      (libsource (lib "eagle-import") (part "MOMENTARY-SWITCH-SPST-LED-PTH-CHERRY"))
    )
    (comp (ref "S75")
      (value "MOMENTARY-SWITCH-SPST-LED-PTH-CHERRY")
      (footprint "eagle-import:CHERRY-MX-LED")
      (libsource (lib "eagle-import") (part "MOMENTARY-SWITCH-SPST-LED-PTH-CHERRY"))
    )
    (comp (ref "S76")
      (value "MOMENTARY-SWITCH-SPST-LED-PTH-CHERRY")
      (footprint "eagle-import:CHERRY-MX-LED")
      (libsource (lib "eagle-import") (part "MOMENTARY-SWITCH-SPST-LED-PTH-CHERRY"))
    )
    (comp (ref "S77")
      (value "MOMENTARY-SWITCH-SPST-LED-PTH-CHERRY")
      (footprint "eagle-import:CHERRY-MX-LED")
      (libsource (lib "eagle-import") (part "MOMENTARY-SWITCH-SPST-LED-PTH-CHERRY"))
    )
    (comp (ref "S78")
      (value "MOMENTARY-SWITCH-SPST-LED-PTH-CHERRY")
      (footprint "eagle-import:CHERRY-MX-LED")
      (libsource (lib "eagle-import") (part "MOMENTARY-SWITCH-SPST-LED-PTH-CHERRY"))
    )
    (comp (ref "S79")
      (value "MOMENTARY-SWITCH-SPST-LED-PTH-CHERRY")
      (footprint "eagle-import:CHERRY-MX-LED")
      (libsource (lib "eagle-import") (part "MOMENTARY-SWITCH-SPST-LED-PTH-CHERRY"))
    )
    (comp (ref "S80")
      (value "MOMENTARY-SWITCH-SPST-SMD-5.2MM")
      (footprint "eagle-import:TACTILE_SWITCH_SMD_5.2MM")
      (libsource (lib "eagle-import") (part "MOMENTARY-SWITCH-SPST-SMD-5.2MM"))
    )
    (comp (ref "U$1")
      (value "USB_TYPE_C")
      (footprint "eagle-import:USB_TYPE_C")
      (libsource (lib "eagle-import") (part "USB_TYPE_C"))
    )
    (comp (ref "Y1")
      (value "16MHz")
      (footprint "eagle-import:CRYSTAL-SMD-5X3.2-4PAD")
      (libsource (lib "eagle-import") (part "CRYSTAL-16MHZSMD-5X3.2"))
    )
  )
  (nets
    (net (code "1") (name "/GND") (class "Default")
      (node (ref "ATMEGA32U4-AU") (pin "15") (pinfunction "GND_2_15") (pintype "passive"))
      (node (ref "ATMEGA32U4-AU") (pin "23") (pinfunction "GND_3_23") (pintype "passive"))
      (node (ref "ATMEGA32U4-AU") (pin "35") (pinfunction "GND_4_35") (pintype "passive"))
      (node (ref "ATMEGA32U4-AU") (pin "43") (pinfunction "GND_43") (pintype "passive"))
      (node (ref "ATMEGA32U4-AU") (pin "5") (pinfunction "UGND_5") (pintype "passive"))
      (node (ref "C1") (pin "2") (pinfunction "2_2") (pintype "passive"))
      (node (ref "C2") (pin "2") (pinfunction "2_2") (pintype "passive"))
      (node (ref "C3") (pin "2") (pinfunction "2_2") (pintype "passive"))
      (node (ref "C4") (pin "2") (pinfunction "2_2") (pintype "passive"))
      (node (ref "D80") (pin "C") (pinfunction "C_C") (pintype "passive"))
      (node (ref "ISP") (pin "6") (pinfunction "6_6") (pintype "bidirectional"))
      (node (ref "R3") (pin "2") (pinfunction "2_2") (pintype "passive"))
      (node (ref "R4") (pin "2") (pinfunction "2_2") (pintype "passive"))
      (node (ref "S80") (pin "1") (pinfunction "1_1") (pintype "passive"))
      (node (ref "U$1") (pin "A12B1GND") (pinfunction "A12B1GND_A12B1GND") (pintype "bidirectional"))
      (node (ref "U$1") (pin "A1B12GND") (pinfunction "A1B12GND_A1B12GND") (pintype "bidirectional"))
    )
    (net (code "2") (name "/VCC") (class "Default")
      (node (ref "ATMEGA32U4-AU") (pin "14") (pinfunction "VCC_2_14") (pintype "power_in"))
      (node (ref "ATMEGA32U4-AU") (pin "2") (pinfunction "UVCC_2") (pintype "power_in"))
      (node (ref "ATMEGA32U4-AU") (pin "24") (pinfunction "AVCC_2_24") (pintype "power_in"))
      (node (ref "ATMEGA32U4-AU") (pin "34") (pinfunction "VCC_34") (pintype "power_in"))
      (node (ref "ATMEGA32U4-AU") (pin "44") (pinfunction "AVCC_44") (pintype "power_in"))
      (node (ref "ATMEGA32U4-AU") (pin "7") (pinfunction "VBUS_7") (pintype "input"))
      (node (ref "C1") (pin "1") (pinfunction "1_1") (pintype "passive"))
      (node (ref "ISP") (pin "2") (pinfunction "2_2") (pintype "bidirectional"))
      (node (ref "U$1") (pin "A4B9VBUS") (pinfunction "A4B9VBUS_A4B9VBUS") (pintype "bidirectional"))
      (node (ref "U$1") (pin "A9B4VBUS") (pinfunction "A9B4VBUS_A9B4VBUS") (pintype "bidirectional"))
    )
    (net (code "3") (name "C1") (class "Default")
      (node (ref "ATMEGA32U4-AU") (pin "8") (pinfunction "PB0_8") (pintype "bidirectional"))
      (node (ref "D1") (pin "C") (pinfunction "C_C") (pintype "passive"))
      (node (ref "D18") (pin "C") (pinfunction "C_C") (pintype "passive"))
      (node (ref "D35") (pin "C") (pinfunction "C_C") (pintype "passive"))
      (node (ref "D51") (pin "C") (pinfunction "C_C") (pintype "passive"))
      (node (ref "D67") (pin "C") (pinfunction "C_C") (pintype "passive"))
    )
    (net (code "4") (name "C2") (class "Default")
      (node (ref "ATMEGA32U4-AU") (pin "9") (pinfunction "PB1_9") (pintype "bidirectional"))
      (node (ref "D19") (pin "C") (pinfunction "C_C") (pintype "passive"))
      (node (ref "D2") (pin "C") (pinfunction "C_C") (pintype "passive"))
      (node (ref "D36") (pin "C") (pinfunction "C_C") (pintype "passive"))
      (node (ref "D52") (pin "C") (pinfunction "C_C") (pintype "passive"))
      (node (ref "D68") (pin "C") (pinfunction "C_C") (pintype "passive"))
      (node (ref "ISP") (pin "3") (pinfunction "3_3") (pintype "bidirectional"))
    )
    (net (code "5") (name "C3") (class "Default")
      (node (ref "ATMEGA32U4-AU") (pin "10") (pinfunction "PB2_10") (pintype "bidirectional"))
      (node (ref "D20") (pin "C") (pinfunction "C_C") (pintype "passive"))
      (node (ref "D3") (pin "C") (pinfunction "C_C") (pintype "passive"))
      (node (ref "D37") (pin "C") (pinfunction "C_C") (pintype "passive"))
      (node (ref "D53") (pin "C") (pinfunction "C_C") (pintype "passive"))
      (node (ref "D69") (pin "C") (pinfunction "C_C") (pintype "passive"))
      (node (ref "ISP") (pin "4") (pinfunction "4_4") (pintype "bidirectional"))
    )
    (net (code "6") (name "C4") (class "Default")
      (node (ref "ATMEGA32U4-AU") (pin "11") (pinfunction "PB3_11") (pintype "bidirectional"))
      (node (ref "D21") (pin "C") (pinfunction "C_C") (pintype "passive"))
      (node (ref "D38") (pin "C") (pinfunction "C_C") (pintype "passive"))
      (node (ref "D4") (pin "C") (pinfunction "C_C") (pintype "passive"))
      (node (ref "D54") (pin "C") (pinfunction "C_C") (pintype "passive"))
      (node (ref "D70") (pin "C") (pinfunction "C_C") (pintype "passive"))
      (node (ref "ISP") (pin "1") (pinfunction "1_1") (pintype "bidirectional"))
    )
    (net (code "7") (name "C5") (class "Default")
      (node (ref "ATMEGA32U4-AU") (pin "28") (pinfunction "PB4_28") (pintype "bidirectional"))
      (node (ref "D22") (pin "C") (pinfunction "C_C") (pintype "passive"))
      (node (ref "D39") (pin "C") (pinfunction "C_C") (pintype "passive"))
      (node (ref "D5") (pin "C") (pinfunction "C_C") (pintype "passive"))
      (node (ref "D55") (pin "C") (pinfunction "C_C") (pintype "passive"))
      (node (ref "D71") (pin "C") (pinfunction "C_C") (pintype "passive"))
    )
    (net (code "8") (name "C6") (class "Default")
      (node (ref "ATMEGA32U4-AU") (pin "29") (pinfunction "PB5_29") (pintype "bidirectional"))
      (node (ref "D23") (pin "C") (pinfunction "C_C") (pintype "passive"))
      (node (ref "D40") (pin "C") (pinfunction "C_C") (pintype "passive"))
      (node (ref "D56") (pin "C") (pinfunction "C_C") (pintype "passive"))
      (node (ref "D6") (pin "C") (pinfunction "C_C") (pintype "passive"))
      (node (ref "D72") (pin "C") (pinfunction "C_C") (pintype "passive"))
    )
    (net (code "9") (name "C7") (class "Default")
      (node (ref "ATMEGA32U4-AU") (pin "30") (pinfunction "PB6_30") (pintype "bidirectional"))
      (node (ref "D24") (pin "C") (pinfunction "C_C") (pintype "passive"))
      (node (ref "D41") (pin "C") (pinfunction "C_C") (pintype "passive"))
      (node (ref "D57") (pin "C") (pinfunction "C_C") (pintype "passive"))
      (node (ref "D7") (pin "C") (pinfunction "C_C") (pintype "passive"))
      (node (ref "D73") (pin "C") (pinfunction "C_C") (pintype "passive"))
    )
    (net (code "10") (name "C8") (class "Default")
      (node (ref "ATMEGA32U4-AU") (pin "12") (pinfunction "PB7_12") (pintype "bidirectional"))
      (node (ref "D25") (pin "C") (pinfunction "C_C") (pintype "passive"))
      (node (ref "D42") (pin "C") (pinfunction "C_C") (pintype "passive"))
      (node (ref "D58") (pin "C") (pinfunction "C_C") (pintype "passive"))
      (node (ref "D74") (pin "C") (pinfunction "C_C") (pintype "passive"))
      (node (ref "D8") (pin "C") (pinfunction "C_C") (pintype "passive"))
    )
    (net (code "11") (name "C9") (class "Default")
      (node (ref "ATMEGA32U4-AU") (pin "31") (pinfunction "PC6_31") (pintype "bidirectional"))
      (node (ref "D26") (pin "C") (pinfunction "C_C") (pintype "passive"))
      (node (ref "D43") (pin "C") (pinfunction "C_C") (pintype "passive"))
      (node (ref "D59") (pin "C") (pinfunction "C_C") (pintype "passive"))
      (node (ref "D75") (pin "C") (pinfunction "C_C") (pintype "passive"))
      (node (ref "D9") (pin "C") (pinfunction "C_C") (pintype "passive"))
    )
    (net (code "12") (name "C10") (class "Default")
      (node (ref "ATMEGA32U4-AU") (pin "32") (pinfunction "PC7_32") (pintype "bidirectional"))
      (node (ref "D10") (pin "C") (pinfunction "C_C") (pintype "passive"))
      (node (ref "D27") (pin "C") (pinfunction "C_C") (pintype "passive"))
      (node (ref "D44") (pin "C") (pinfunction "C_C") (pintype "passive"))
      (node (ref "D60") (pin "C") (pinfunction "C_C") (pintype "passive"))
      (node (ref "D76") (pin "C") (pinfunction "C_C") (pintype "passive"))
    )
    (net (code "13") (name "C11") (class "Default")
      (node (ref "ATMEGA32U4-AU") (pin "18") (pinfunction "PD0_18") (pintype "bidirectional"))
      (node (ref "D11") (pin "C") (pinfunction "C_C") (pintype "passive"))
      (node (ref "D28") (pin "C") (pinfunction "C_C") (pintype "passive"))
      (node (ref "D45") (pin "C") (pinfunction "C_C") (pintype "passive"))
      (node (ref "D61") (pin "C") (pinfunction "C_C") (pintype "passive"))
      (node (ref "D77") (pin "C") (pinfunction "C_C") (pintype "passive"))
    )
    (net (code "14") (name "C12") (class "Default")
      (node (ref "ATMEGA32U4-AU") (pin "19") (pinfunction "PD1_19") (pintype "bidirectional"))
      (node (ref "D12") (pin "C") (pinfunction "C_C") (pintype "passive"))
      (node (ref "D29") (pin "C") (pinfunction "C_C") (pintype "passive"))
      (node (ref "D46") (pin "C") (pinfunction "C_C") (pintype "passive"))
      (node (ref "D62") (pin "C") (pinfunction "C_C") (pintype "passive"))
      (node (ref "D78") (pin "C") (pinfunction "C_C") (pintype "passive"))
    )
    (net (code "15") (name "C13") (class "Default")
      (node (ref "ATMEGA32U4-AU") (pin "20") (pinfunction "PD2_20") (pintype "bidirectional"))
      (node (ref "D13") (pin "C") (pinfunction "C_C") (pintype "passive"))
      (node (ref "D30") (pin "C") (pinfunction "C_C") (pintype "passive"))
      (node (ref "D47") (pin "C") (pinfunction "C_C") (pintype "passive"))
      (node (ref "D63") (pin "C") (pinfunction "C_C") (pintype "passive"))
      (node (ref "D79") (pin "C") (pinfunction "C_C") (pintype "passive"))
    )
    (net (code "16") (name "C14") (class "Default")
      (node (ref "ATMEGA32U4-AU") (pin "21") (pinfunction "PD3_21") (pintype "bidirectional"))
      (node (ref "D14") (pin "C") (pinfunction "C_C") (pintype "passive"))
      (node (ref "D31") (pin "C") (pinfunction "C_C") (pintype "passive"))
      (node (ref "D48") (pin "C") (pinfunction "C_C") (pintype "passive"))
      (node (ref "D64") (pin "C") (pinfunction "C_C") (pintype "passive"))
    )
    (net (code "17") (name "C15") (class "Default")
      (node (ref "ATMEGA32U4-AU") (pin "25") (pinfunction "PD4_25") (pintype "bidirectional"))
      (node (ref "D15") (pin "C") (pinfunction "C_C") (pintype "passive"))
      (node (ref "D32") (pin "C") (pinfunction "C_C") (pintype "passive"))
      (node (ref "D49") (pin "C") (pinfunction "C_C") (pintype "passive"))
      (node (ref "D65") (pin "C") (pinfunction "C_C") (pintype "passive"))
    )
    (net (code "18") (name "C16") (class "Default")
      (node (ref "ATMEGA32U4-AU") (pin "22") (pinfunction "PD5_22") (pintype "bidirectional"))
      (node (ref "D16") (pin "C") (pinfunction "C_C") (pintype "passive"))
      (node (ref "D33") (pin "C") (pinfunction "C_C") (pintype "passive"))
      (node (ref "D50") (pin "C") (pinfunction "C_C") (pintype "passive"))
      (node (ref "D66") (pin "C") (pinfunction "C_C") (pintype "passive"))
    )
    (net (code "19") (name "C17") (class "Default")
      (node (ref "ATMEGA32U4-AU") (pin "27") (pinfunction "PD7_27") (pintype "bidirectional"))
      (node (ref "D17") (pin "C") (pinfunction "C_C") (pintype "passive"))
      (node (ref "D34") (pin "C") (pinfunction "C_C") (pintype "passive"))
    )
    (net (code "20") (name "Net-(ATMEGA32U4-AU-D+)") (class "Default")
      (node (ref "ATMEGA32U4-AU") (pin "4") (pinfunction "D+_4") (pintype "passive"))
      (node (ref "R2") (pin "2") (pinfunction "2_2") (pintype "passive"))
    )
    (net (code "21") (name "Net-(ATMEGA32U4-AU-D-)") (class "Default")
      (node (ref "ATMEGA32U4-AU") (pin "3") (pinfunction "D-_3") (pintype "passive"))
      (node (ref "R1") (pin "2") (pinfunction "2_2") (pintype "passive"))
    )
    (net (code "22") (name "Net-(ATMEGA32U4-AU-PE6)") (class "Default")
      (node (ref "ATMEGA32U4-AU") (pin "1") (pinfunction "PE6_1") (pintype "bidirectional"))
      (node (ref "R5") (pin "1") (pinfunction "1_1") (pintype "passive"))
    )
    (net (code "23") (name "Net-(ATMEGA32U4-AU-UCAP)") (class "Default")
      (node (ref "ATMEGA32U4-AU") (pin "6") (pinfunction "UCAP_6") (pintype "power_in"))
      (node (ref "C4") (pin "1") (pinfunction "1_1") (pintype "passive"))
    )
    (net (code "24") (name "Net-(ATMEGA32U4-AU-XTAL1)") (class "Default")
      (node (ref "ATMEGA32U4-AU") (pin "17") (pinfunction "XTAL1_17") (pintype "input"))
      (node (ref "C2") (pin "1") (pinfunction "1_1") (pintype "passive"))
      (node (ref "Y1") (pin "1") (pinfunction "1_1") (pintype "passive"))
    )
    (net (code "25") (name "Net-(ATMEGA32U4-AU-XTAL2)") (class "Default")
      (node (ref "ATMEGA32U4-AU") (pin "16") (pinfunction "XTAL2_16") (pintype "output"))
      (node (ref "C3") (pin "1") (pinfunction "1_1") (pintype "passive"))
      (node (ref "Y1") (pin "3") (pinfunction "2_3") (pintype "passive"))
    )
    (net (code "26") (name "Net-(ATMEGA32U4-AU-~{RESET})") (class "Default")
      (node (ref "ATMEGA32U4-AU") (pin "13") (pinfunction "~{RESET}_13") (pintype "input"))
      (node (ref "ISP") (pin "5") (pinfunction "5_5") (pintype "bidirectional"))
      (node (ref "S80") (pin "3") (pinfunction "2_3") (pintype "passive"))
    )
    (net (code "27") (name "Net-(D80-PadA)") (class "Default")
      (node (ref "D80") (pin "A") (pinfunction "A_A") (pintype "passive"))
      (node (ref "R5") (pin "2") (pinfunction "2_2") (pintype "passive"))
    )
    (net (code "28") (name "Net-(S1-2)") (class "Default")
      (node (ref "D1") (pin "A") (pinfunction "A_A") (pintype "passive"))
      (node (ref "S1") (pin "S2") (pinfunction "2_S2") (pintype "passive"))
    )
    (net (code "29") (name "Net-(S2-2)") (class "Default")
      (node (ref "D2") (pin "A") (pinfunction "A_A") (pintype "passive"))
      (node (ref "S2") (pin "S2") (pinfunction "2_S2") (pintype "passive"))
    )
    (net (code "30") (name "Net-(S3-2)") (class "Default")
      (node (ref "D3") (pin "A") (pinfunction "A_A") (pintype "passive"))
      (node (ref "S3") (pin "S2") (pinfunction "2_S2") (pintype "passive"))
    )
    (net (code "31") (name "Net-(S4-2)") (class "Default")
      (node (ref "D4") (pin "A") (pinfunction "A_A") (pintype "passive"))
      (node (ref "S4") (pin "S2") (pinfunction "2_S2") (pintype "passive"))
    )
    (net (code "32") (name "Net-(S5-2)") (class "Default")
      (node (ref "D5") (pin "A") (pinfunction "A_A") (pintype "passive"))
      (node (ref "S5") (pin "S2") (pinfunction "2_S2") (pintype "passive"))
    )
    (net (code "33") (name "Net-(S6-2)") (class "Default")
      (node (ref "D6") (pin "A") (pinfunction "A_A") (pintype "passive"))
      (node (ref "S6") (pin "S2") (pinfunction "2_S2") (pintype "passive"))
    )
    (net (code "34") (name "Net-(S7-2)") (class "Default")
      (node (ref "D7") (pin "A") (pinfunction "A_A") (pintype "passive"))
      (node (ref "S7") (pin "S2") (pinfunction "2_S2") (pintype "passive"))
    )
    (net (code "35") (name "Net-(S8-2)") (class "Default")
      (node (ref "D8") (pin "A") (pinfunction "A_A") (pintype "passive"))
      (node (ref "S8") (pin "S2") (pinfunction "2_S2") (pintype "passive"))
    )
    (net (code "36") (name "Net-(S9-2)") (class "Default")
      (node (ref "D9") (pin "A") (pinfunction "A_A") (pintype "passive"))
      (node (ref "S9") (pin "S2") (pinfunction "2_S2") (pintype "passive"))
    )
    (net (code "37") (name "Net-(S10-2)") (class "Default")
      (node (ref "D10") (pin "A") (pinfunction "A_A") (pintype "passive"))
      (node (ref "S10") (pin "S2") (pinfunction "2_S2") (pintype "passive"))
    )
    (net (code "38") (name "Net-(S11-2)") (class "Default")
      (node (ref "D11") (pin "A") (pinfunction "A_A") (pintype "passive"))
      (node (ref "S11") (pin "S2") (pinfunction "2_S2") (pintype "passive"))
    )
    (net (code "39") (name "Net-(S12-2)") (class "Default")
      (node (ref "D12") (pin "A") (pinfunction "A_A") (pintype "passive"))
      (node (ref "S12") (pin "S2") (pinfunction "2_S2") (pintype "passive"))
    )
    (net (code "40") (name "Net-(S13-2)") (class "Default")
      (node (ref "D13") (pin "A") (pinfunction "A_A") (pintype "passive"))
      (node (ref "S13") (pin "S2") (pinfunction "2_S2") (pintype "passive"))
    )
    (net (code "41") (name "Net-(S14-2)") (class "Default")
      (node (ref "D14") (pin "A") (pinfunction "A_A") (pintype "passive"))
      (node (ref "S14") (pin "S2") (pinfunction "2_S2") (pintype "passive"))
    )
    (net (code "42") (name "Net-(S15-2)") (class "Default")
      (node (ref "D15") (pin "A") (pinfunction "A_A") (pintype "passive"))
      (node (ref "S15") (pin "S2") (pinfunction "2_S2") (pintype "passive"))
    )
    (net (code "43") (name "Net-(S16-2)") (class "Default")
      (node (ref "D16") (pin "A") (pinfunction "A_A") (pintype "passive"))
      (node (ref "S16") (pin "S2") (pinfunction "2_S2") (pintype "passive"))
    )
    (net (code "44") (name "Net-(S17-2)") (class "Default")
      (node (ref "D17") (pin "A") (pinfunction "A_A") (pintype "passive"))
      (node (ref "S17") (pin "S2") (pinfunction "2_S2") (pintype "passive"))
    )
    (net (code "45") (name "Net-(S18-2)") (class "Default")
      (node (ref "D18") (pin "A") (pinfunction "A_A") (pintype "passive"))
      (node (ref "S18") (pin "S2") (pinfunction "2_S2") (pintype "passive"))
    )
    (net (code "46") (name "Net-(S19-2)") (class "Default")
      (node (ref "D19") (pin "A") (pinfunction "A_A") (pintype "passive"))
      (node (ref "S19") (pin "S2") (pinfunction "2_S2") (pintype "passive"))
    )
    (net (code "47") (name "Net-(S20-2)") (class "Default")
      (node (ref "D20") (pin "A") (pinfunction "A_A") (pintype "passive"))
      (node (ref "S20") (pin "S2") (pinfunction "2_S2") (pintype "passive"))
    )
    (net (code "48") (name "Net-(S21-2)") (class "Default")
      (node (ref "D21") (pin "A") (pinfunction "A_A") (pintype "passive"))
      (node (ref "S21") (pin "S2") (pinfunction "2_S2") (pintype "passive"))
    )
    (net (code "49") (name "Net-(S22-2)") (class "Default")
      (node (ref "D22") (pin "A") (pinfunction "A_A") (pintype "passive"))
      (node (ref "S22") (pin "S2") (pinfunction "2_S2") (pintype "passive"))
    )
    (net (code "50") (name "Net-(S23-2)") (class "Default")
      (node (ref "D23") (pin "A") (pinfunction "A_A") (pintype "passive"))
      (node (ref "S23") (pin "S2") (pinfunction "2_S2") (pintype "passive"))
    )
    (net (code "51") (name "Net-(S24-2)") (class "Default")
      (node (ref "D24") (pin "A") (pinfunction "A_A") (pintype "passive"))
      (node (ref "S24") (pin "S2") (pinfunction "2_S2") (pintype "passive"))
    )
    (net (code "52") (name "Net-(S25-2)") (class "Default")
      (node (ref "D25") (pin "A") (pinfunction "A_A") (pintype "passive"))
      (node (ref "S25") (pin "S2") (pinfunction "2_S2") (pintype "passive"))
    )
    (net (code "53") (name "Net-(S26-2)") (class "Default")
      (node (ref "D26") (pin "A") (pinfunction "A_A") (pintype "passive"))
      (node (ref "S26") (pin "S2") (pinfunction "2_S2") (pintype "passive"))
    )
    (net (code "54") (name "Net-(S27-2)") (class "Default")
      (node (ref "D27") (pin "A") (pinfunction "A_A") (pintype "passive"))
      (node (ref "S27") (pin "S2") (pinfunction "2_S2") (pintype "passive"))
    )
    (net (code "55") (name "Net-(S28-2)") (class "Default")
      (node (ref "D28") (pin "A") (pinfunction "A_A") (pintype "passive"))
      (node (ref "S28") (pin "S2") (pinfunction "2_S2") (pintype "passive"))
    )
    (net (code "56") (name "Net-(S29-2)") (class "Default")
      (node (ref "D29") (pin "A") (pinfunction "A_A") (pintype "passive"))
      (node (ref "S29") (pin "S2") (pinfunction "2_S2") (pintype "passive"))
    )
    (net (code "57") (name "Net-(S30-2)") (class "Default")
      (node (ref "D30") (pin "A") (pinfunction "A_A") (pintype "passive"))
      (node (ref "S30") (pin "S2") (pinfunction "2_S2") (pintype "passive"))
    )
    (net (code "58") (name "Net-(S31-2)") (class "Default")
      (node (ref "D31") (pin "A") (pinfunction "A_A") (pintype "passive"))
      (node (ref "S31") (pin "S2") (pinfunction "2_S2") (pintype "passive"))
    )
    (net (code "59") (name "Net-(S32-2)") (class "Default")
      (node (ref "D32") (pin "A") (pinfunction "A_A") (pintype "passive"))
      (node (ref "S32") (pin "S2") (pinfunction "2_S2") (pintype "passive"))
    )
    (net (code "60") (name "Net-(S33-2)") (class "Default")
      (node (ref "D33") (pin "A") (pinfunction "A_A") (pintype "passive"))
      (node (ref "S33") (pin "S2") (pinfunction "2_S2") (pintype "passive"))
    )
    (net (code "61") (name "Net-(S34-2)") (class "Default")
      (node (ref "D34") (pin "A") (pinfunction "A_A") (pintype "passive"))
      (node (ref "S34") (pin "S2") (pinfunction "2_S2") (pintype "passive"))
    )
    (net (code "62") (name "Net-(S35-2)") (class "Default")
      (node (ref "D35") (pin "A") (pinfunction "A_A") (pintype "passive"))
      (node (ref "S35") (pin "S2") (pinfunction "2_S2") (pintype "passive"))
    )
    (net (code "63") (name "Net-(S36-2)") (class "Default")
      (node (ref "D36") (pin "A") (pinfunction "A_A") (pintype "passive"))
      (node (ref "S36") (pin "S2") (pinfunction "2_S2") (pintype "passive"))
    )
    (net (code "64") (name "Net-(S37-2)") (class "Default")
      (node (ref "D37") (pin "A") (pinfunction "A_A") (pintype "passive"))
      (node (ref "S37") (pin "S2") (pinfunction "2_S2") (pintype "passive"))
    )
    (net (code "65") (name "Net-(S38-2)") (class "Default")
      (node (ref "D38") (pin "A") (pinfunction "A_A") (pintype "passive"))
      (node (ref "S38") (pin "S2") (pinfunction "2_S2") (pintype "passive"))
    )
    (net (code "66") (name "Net-(S39-2)") (class "Default")
      (node (ref "D39") (pin "A") (pinfunction "A_A") (pintype "passive"))
      (node (ref "S39") (pin "S2") (pinfunction "2_S2") (pintype "passive"))
    )
    (net (code "67") (name "Net-(S40-2)") (class "Default")
      (node (ref "D40") (pin "A") (pinfunction "A_A") (pintype "passive"))
      (node (ref "S40") (pin "S2") (pinfunction "2_S2") (pintype "passive"))
    )
    (net (code "68") (name "Net-(S41-2)") (class "Default")
      (node (ref "D41") (pin "A") (pinfunction "A_A") (pintype "passive"))
      (node (ref "S41") (pin "S2") (pinfunction "2_S2") (pintype "passive"))
    )
    (net (code "69") (name "Net-(S42-2)") (class "Default")
      (node (ref "D42") (pin "A") (pinfunction "A_A") (pintype "passive"))
      (node (ref "S42") (pin "S2") (pinfunction "2_S2") (pintype "passive"))
    )
    (net (code "70") (name "Net-(S43-2)") (class "Default")
      (node (ref "D43") (pin "A") (pinfunction "A_A") (pintype "passive"))
      (node (ref "S43") (pin "S2") (pinfunction "2_S2") (pintype "passive"))
    )
    (net (code "71") (name "Net-(S44-2)") (class "Default")
      (node (ref "D44") (pin "A") (pinfunction "A_A") (pintype "passive"))
      (node (ref "S44") (pin "S2") (pinfunction "2_S2") (pintype "passive"))
    )
    (net (code "72") (name "Net-(S45-2)") (class "Default")
      (node (ref "D45") (pin "A") (pinfunction "A_A") (pintype "passive"))
      (node (ref "S45") (pin "S2") (pinfunction "2_S2") (pintype "passive"))
    )
    (net (code "73") (name "Net-(S46-2)") (class "Default")
      (node (ref "D46") (pin "A") (pinfunction "A_A") (pintype "passive"))
      (node (ref "S46") (pin "S2") (pinfunction "2_S2") (pintype "passive"))
    )
    (net (code "74") (name "Net-(S47-2)") (class "Default")
      (node (ref "D47") (pin "A") (pinfunction "A_A") (pintype "passive"))
      (node (ref "S47") (pin "S2") (pinfunction "2_S2") (pintype "passive"))
    )
    (net (code "75") (name "Net-(S48-2)") (class "Default")
      (node (ref "D48") (pin "A") (pinfunction "A_A") (pintype "passive"))
      (node (ref "S48") (pin "S2") (pinfunction "2_S2") (pintype "passive"))
    )
    (net (code "76") (name "Net-(S49-2)") (class "Default")
      (node (ref "D49") (pin "A") (pinfunction "A_A") (pintype "passive"))
      (node (ref "S49") (pin "S2") (pinfunction "2_S2") (pintype "passive"))
    )
    (net (code "77") (name "Net-(S50-2)") (class "Default")
      (node (ref "D50") (pin "A") (pinfunction "A_A") (pintype "passive"))
      (node (ref "S50") (pin "S2") (pinfunction "2_S2") (pintype "passive"))
    )
    (net (code "78") (name "Net-(S51-2)") (class "Default")
      (node (ref "D51") (pin "A") (pinfunction "A_A") (pintype "passive"))
      (node (ref "S51") (pin "S2") (pinfunction "2_S2") (pintype "passive"))
    )
    (net (code "79") (name "Net-(S52-2)") (class "Default")
      (node (ref "D52") (pin "A") (pinfunction "A_A") (pintype "passive"))
      (node (ref "S52") (pin "S2") (pinfunction "2_S2") (pintype "passive"))
    )
    (net (code "80") (name "Net-(S53-2)") (class "Default")
      (node (ref "D53") (pin "A") (pinfunction "A_A") (pintype "passive"))
      (node (ref "S53") (pin "S2") (pinfunction "2_S2") (pintype "passive"))
    )
    (net (code "81") (name "Net-(S54-2)") (class "Default")
      (node (ref "D54") (pin "A") (pinfunction "A_A") (pintype "passive"))
      (node (ref "S54") (pin "S2") (pinfunction "2_S2") (pintype "passive"))
    )
    (net (code "82") (name "Net-(S55-2)") (class "Default")
      (node (ref "D55") (pin "A") (pinfunction "A_A") (pintype "passive"))
      (node (ref "S55") (pin "S2") (pinfunction "2_S2") (pintype "passive"))
    )
    (net (code "83") (name "Net-(S56-2)") (class "Default")
      (node (ref "D56") (pin "A") (pinfunction "A_A") (pintype "passive"))
      (node (ref "S56") (pin "S2") (pinfunction "2_S2") (pintype "passive"))
    )
    (net (code "84") (name "Net-(S57-2)") (class "Default")
      (node (ref "D57") (pin "A") (pinfunction "A_A") (pintype "passive"))
      (node (ref "S57") (pin "S2") (pinfunction "2_S2") (pintype "passive"))
    )
    (net (code "85") (name "Net-(S58-2)") (class "Default")
      (node (ref "D58") (pin "A") (pinfunction "A_A") (pintype "passive"))
      (node (ref "S58") (pin "S2") (pinfunction "2_S2") (pintype "passive"))
    )
    (net (code "86") (name "Net-(S59-2)") (class "Default")
      (node (ref "D59") (pin "A") (pinfunction "A_A") (pintype "passive"))
      (node (ref "S59") (pin "S2") (pinfunction "2_S2") (pintype "passive"))
    )
    (net (code "87") (name "Net-(S60-2)") (class "Default")
      (node (ref "D60") (pin "A") (pinfunction "A_A") (pintype "passive"))
      (node (ref "S60") (pin "S2") (pinfunction "2_S2") (pintype "passive"))
    )
    (net (code "88") (name "Net-(S61-2)") (class "Default")
      (node (ref "D61") (pin "A") (pinfunction "A_A") (pintype "passive"))
      (node (ref "S61") (pin "S2") (pinfunction "2_S2") (pintype "passive"))
    )
    (net (code "89") (name "Net-(S62-2)") (class "Default")
      (node (ref "D62") (pin "A") (pinfunction "A_A") (pintype "passive"))
      (node (ref "S62") (pin "S2") (pinfunction "2_S2") (pintype "passive"))
    )
    (net (code "90") (name "Net-(S63-2)") (class "Default")
      (node (ref "D63") (pin "A") (pinfunction "A_A") (pintype "passive"))
      (node (ref "S63") (pin "S2") (pinfunction "2_S2") (pintype "passive"))
    )
    (net (code "91") (name "Net-(S64-2)") (class "Default")
      (node (ref "D64") (pin "A") (pinfunction "A_A") (pintype "passive"))
      (node (ref "S64") (pin "S2") (pinfunction "2_S2") (pintype "passive"))
    )
    (net (code "92") (name "Net-(S65-2)") (class "Default")
      (node (ref "D65") (pin "A") (pinfunction "A_A") (pintype "passive"))
      (node (ref "S65") (pin "S2") (pinfunction "2_S2") (pintype "passive"))
    )
    (net (code "93") (name "Net-(S66-2)") (class "Default")
      (node (ref "D66") (pin "A") (pinfunction "A_A") (pintype "passive"))
      (node (ref "S66") (pin "S2") (pinfunction "2_S2") (pintype "passive"))
    )
    (net (code "94") (name "Net-(S67-2)") (class "Default")
      (node (ref "D67") (pin "A") (pinfunction "A_A") (pintype "passive"))
      (node (ref "S67") (pin "S2") (pinfunction "2_S2") (pintype "passive"))
    )
    (net (code "95") (name "Net-(S68-2)") (class "Default")
      (node (ref "D68") (pin "A") (pinfunction "A_A") (pintype "passive"))
      (node (ref "S68") (pin "S2") (pinfunction "2_S2") (pintype "passive"))
    )
    (net (code "96") (name "Net-(S69-2)") (class "Default")
      (node (ref "D69") (pin "A") (pinfunction "A_A") (pintype "passive"))
      (node (ref "S69") (pin "S2") (pinfunction "2_S2") (pintype "passive"))
    )
    (net (code "97") (name "Net-(S70-2)") (class "Default")
      (node (ref "D70") (pin "A") (pinfunction "A_A") (pintype "passive"))
      (node (ref "S70") (pin "S2") (pinfunction "2_S2") (pintype "passive"))
    )
    (net (code "98") (name "Net-(S71-2)") (class "Default")
      (node (ref "D71") (pin "A") (pinfunction "A_A") (pintype "passive"))
      (node (ref "S71") (pin "S2") (pinfunction "2_S2") (pintype "passive"))
    )
    (net (code "99") (name "Net-(S72-2)") (class "Default")
      (node (ref "D72") (pin "A") (pinfunction "A_A") (pintype "passive"))
      (node (ref "S72") (pin "S2") (pinfunction "2_S2") (pintype "passive"))
    )
    (net (code "100") (name "Net-(S73-2)") (class "Default")
      (node (ref "D73") (pin "A") (pinfunction "A_A") (pintype "passive"))
      (node (ref "S73") (pin "S2") (pinfunction "2_S2") (pintype "passive"))
    )
    (net (code "101") (name "Net-(S74-2)") (class "Default")
      (node (ref "D74") (pin "A") (pinfunction "A_A") (pintype "passive"))
      (node (ref "S74") (pin "S2") (pinfunction "2_S2") (pintype "passive"))
    )
    (net (code "102") (name "Net-(S75-2)") (class "Default")
      (node (ref "D75") (pin "A") (pinfunction "A_A") (pintype "passive"))
      (node (ref "S75") (pin "S2") (pinfunction "2_S2") (pintype "passive"))
    )
    (net (code "103") (name "Net-(S76-2)") (class "Default")
      (node (ref "D76") (pin "A") (pinfunction "A_A") (pintype "passive"))
      (node (ref "S76") (pin "S2") (pinfunction "2_S2") (pintype "passive"))
    )
    (net (code "104") (name "Net-(S77-2)") (class "Default")
      (node (ref "D77") (pin "A") (pinfunction "A_A") (pintype "passive"))
      (node (ref "S77") (pin "S2") (pinfunction "2_S2") (pintype "passive"))
    )
    (net (code "105") (name "Net-(S78-2)") (class "Default")
      (node (ref "D78") (pin "A") (pinfunction "A_A") (pintype "passive"))
      (node (ref "S78") (pin "S2") (pinfunction "2_S2") (pintype "passive"))
    )
    (net (code "106") (name "Net-(S79-2)") (class "Default")
      (node (ref "D79") (pin "A") (pinfunction "A_A") (pintype "passive"))
      (node (ref "S79") (pin "S2") (pinfunction "2_S2") (pintype "passive"))
    )
    (net (code "107") (name "Net-(U$1-A5CC1)") (class "Default")
      (node (ref "R3") (pin "1") (pinfunction "1_1") (pintype "passive"))
      (node (ref "U$1") (pin "A5") (pinfunction "A5CC1_A5") (pintype "bidirectional"))
    )
    (net (code "108") (name "Net-(U$1-A6DP1)") (class "Default")
      (node (ref "R2") (pin "1") (pinfunction "1_1") (pintype "passive"))
      (node (ref "U$1") (pin "A6") (pinfunction "A6DP1_A6") (pintype "bidirectional"))
      (node (ref "U$1") (pin "B6") (pinfunction "B6DP2_B6") (pintype "bidirectional"))
    )
    (net (code "109") (name "Net-(U$1-A7DN1)") (class "Default")
      (node (ref "R1") (pin "1") (pinfunction "1_1") (pintype "passive"))
      (node (ref "U$1") (pin "A7") (pinfunction "A7DN1_A7") (pintype "bidirectional"))
      (node (ref "U$1") (pin "B7") (pinfunction "B7DN2_B7") (pintype "bidirectional"))
    )
    (net (code "110") (name "Net-(U$1-B5CC2)") (class "Default")
      (node (ref "R4") (pin "1") (pinfunction "1_1") (pintype "passive"))
      (node (ref "U$1") (pin "B5") (pinfunction "B5CC2_B5") (pintype "bidirectional"))
    )
    (net (code "111") (name "R1") (class "Default")
      (node (ref "ATMEGA32U4-AU") (pin "41") (pinfunction "PF0_41") (pintype "bidirectional"))
      (node (ref "S1") (pin "S1") (pinfunction "1_S1") (pintype "passive"))
      (node (ref "S10") (pin "S1") (pinfunction "1_S1") (pintype "passive"))
      (node (ref "S11") (pin "S1") (pinfunction "1_S1") (pintype "passive"))
      (node (ref "S12") (pin "S1") (pinfunction "1_S1") (pintype "passive"))
      (node (ref "S13") (pin "S1") (pinfunction "1_S1") (pintype "passive"))
      (node (ref "S14") (pin "S1") (pinfunction "1_S1") (pintype "passive"))
      (node (ref "S15") (pin "S1") (pinfunction "1_S1") (pintype "passive"))
      (node (ref "S16") (pin "S1") (pinfunction "1_S1") (pintype "passive"))
      (node (ref "S17") (pin "S1") (pinfunction "1_S1") (pintype "passive"))
      (node (ref "S2") (pin "S1") (pinfunction "1_S1") (pintype "passive"))
      (node (ref "S3") (pin "S1") (pinfunction "1_S1") (pintype "passive"))
      (node (ref "S4") (pin "S1") (pinfunction "1_S1") (pintype "passive"))
      (node (ref "S5") (pin "S1") (pinfunction "1_S1") (pintype "passive"))
      (node (ref "S6") (pin "S1") (pinfunction "1_S1") (pintype "passive"))
      (node (ref "S7") (pin "S1") (pinfunction "1_S1") (pintype "passive"))
      (node (ref "S8") (pin "S1") (pinfunction "1_S1") (pintype "passive"))
      (node (ref "S9") (pin "S1") (pinfunction "1_S1") (pintype "passive"))
    )
    (net (code "112") (name "R2") (class "Default")
      (node (ref "ATMEGA32U4-AU") (pin "40") (pinfunction "PF1_40") (pintype "bidirectional"))
      (node (ref "S18") (pin "S1") (pinfunction "1_S1") (pintype "passive"))
      (node (ref "S19") (pin "S1") (pinfunction "1_S1") (pintype "passive"))
      (node (ref "S20") (pin "S1") (pinfunction "1_S1") (pintype "passive"))
      (node (ref "S21") (pin "S1") (pinfunction "1_S1") (pintype "passive"))
      (node (ref "S22") (pin "S1") (pinfunction "1_S1") (pintype "passive"))
      (node (ref "S23") (pin "S1") (pinfunction "1_S1") (pintype "passive"))
      (node (ref "S24") (pin "S1") (pinfunction "1_S1") (pintype "passive"))
      (node (ref "S25") (pin "S1") (pinfunction "1_S1") (pintype "passive"))
      (node (ref "S26") (pin "S1") (pinfunction "1_S1") (pintype "passive"))
      (node (ref "S27") (pin "S1") (pinfunction "1_S1") (pintype "passive"))
      (node (ref "S28") (pin "S1") (pinfunction "1_S1") (pintype "passive"))
      (node (ref "S29") (pin "S1") (pinfunction "1_S1") (pintype "passive"))
      (node (ref "S30") (pin "S1") (pinfunction "1_S1") (pintype "passive"))
      (node (ref "S31") (pin "S1") (pinfunction "1_S1") (pintype "passive"))
      (node (ref "S32") (pin "S1") (pinfunction "1_S1") (pintype "passive"))
      (node (ref "S33") (pin "S1") (pinfunction "1_S1") (pintype "passive"))
      (node (ref "S34") (pin "S1") (pinfunction "1_S1") (pintype "passive"))
    )
    (net (code "113") (name "R3") (class "Default")
      (node (ref "ATMEGA32U4-AU") (pin "39") (pinfunction "PF4_39") (pintype "bidirectional"))
      (node (ref "S35") (pin "S1") (pinfunction "1_S1") (pintype "passive"))
      (node (ref "S36") (pin "S1") (pinfunction "1_S1") (pintype "passive"))
      (node (ref "S37") (pin "S1") (pinfunction "1_S1") (pintype "passive"))
      (node (ref "S38") (pin "S1") (pinfunction "1_S1") (pintype "passive"))
      (node (ref "S39") (pin "S1") (pinfunction "1_S1") (pintype "passive"))
      (node (ref "S40") (pin "S1") (pinfunction "1_S1") (pintype "passive"))
      (node (ref "S41") (pin "S1") (pinfunction "1_S1") (pintype "passive"))
      (node (ref "S42") (pin "S1") (pinfunction "1_S1") (pintype "passive"))
      (node (ref "S43") (pin "S1") (pinfunction "1_S1") (pintype "passive"))
      (node (ref "S44") (pin "S1") (pinfunction "1_S1") (pintype "passive"))
      (node (ref "S45") (pin "S1") (pinfunction "1_S1") (pintype "passive"))
      (node (ref "S46") (pin "S1") (pinfunction "1_S1") (pintype "passive"))
      (node (ref "S47") (pin "S1") (pinfunction "1_S1") (pintype "passive"))
      (node (ref "S48") (pin "S1") (pinfunction "1_S1") (pintype "passive"))
      (node (ref "S49") (pin "S1") (pinfunction "1_S1") (pintype "passive"))
      (node (ref "S50") (pin "S1") (pinfunction "1_S1") (pintype "passive"))
    )
    (net (code "114") (name "R4") (class "Default")
      (node (ref "ATMEGA32U4-AU") (pin "38") (pinfunction "PF5_38") (pintype "bidirectional"))
      (node (ref "S51") (pin "S1") (pinfunction "1_S1") (pintype "passive"))
      (node (ref "S52") (pin "S1") (pinfunction "1_S1") (pintype "passive"))
      (node (ref "S53") (pin "S1") (pinfunction "1_S1") (pintype "passive"))
      (node (ref "S54") (pin "S1") (pinfunction "1_S1") (pintype "passive"))
      (node (ref "S55") (pin "S1") (pinfunction "1_S1") (pintype "passive"))
      (node (ref "S56") (pin "S1") (pinfunction "1_S1") (pintype "passive"))
      (node (ref "S57") (pin "S1") (pinfunction "1_S1") (pintype "passive"))
      (node (ref "S58") (pin "S1") (pinfunction "1_S1") (pintype "passive"))
      (node (ref "S59") (pin "S1") (pinfunction "1_S1") (pintype "passive"))
      (node (ref "S60") (pin "S1") (pinfunction "1_S1") (pintype "passive"))
      (node (ref "S61") (pin "S1") (pinfunction "1_S1") (pintype "passive"))
      (node (ref "S62") (pin "S1") (pinfunction "1_S1") (pintype "passive"))
      (node (ref "S63") (pin "S1") (pinfunction "1_S1") (pintype "passive"))
      (node (ref "S64") (pin "S1") (pinfunction "1_S1") (pintype "passive"))
      (node (ref "S65") (pin "S1") (pinfunction "1_S1") (pintype "passive"))
      (node (ref "S66") (pin "S1") (pinfunction "1_S1") (pintype "passive"))
    )
    (net (code "115") (name "R5") (class "Default")
      (node (ref "ATMEGA32U4-AU") (pin "37") (pinfunction "PF6_37") (pintype "bidirectional"))
      (node (ref "S67") (pin "S1") (pinfunction "1_S1") (pintype "passive"))
      (node (ref "S68") (pin "S1") (pinfunction "1_S1") (pintype "passive"))
      (node (ref "S69") (pin "S1") (pinfunction "1_S1") (pintype "passive"))
      (node (ref "S70") (pin "S1") (pinfunction "1_S1") (pintype "passive"))
      (node (ref "S71") (pin "S1") (pinfunction "1_S1") (pintype "passive"))
      (node (ref "S72") (pin "S1") (pinfunction "1_S1") (pintype "passive"))
      (node (ref "S73") (pin "S1") (pinfunction "1_S1") (pintype "passive"))
      (node (ref "S74") (pin "S1") (pinfunction "1_S1") (pintype "passive"))
      (node (ref "S75") (pin "S1") (pinfunction "1_S1") (pintype "passive"))
      (node (ref "S76") (pin "S1") (pinfunction "1_S1") (pintype "passive"))
      (node (ref "S77") (pin "S1") (pinfunction "1_S1") (pintype "passive"))
      (node (ref "S78") (pin "S1") (pinfunction "1_S1") (pintype "passive"))
      (node (ref "S79") (pin "S1") (pinfunction "1_S1") (pintype "passive"))
    )
    (net (code "116") (name "unconnected-(ATMEGA32U4-AU-AREF-Pad42)") (class "Default")
      (node (ref "ATMEGA32U4-AU") (pin "42") (pinfunction "AREF_42") (pintype "input"))
    )
    (net (code "117") (name "unconnected-(ATMEGA32U4-AU-PD6-Pad26)") (class "Default")
      (node (ref "ATMEGA32U4-AU") (pin "26") (pinfunction "PD6_26") (pintype "bidirectional"))
    )
    (net (code "118") (name "unconnected-(ATMEGA32U4-AU-PE2-Pad33)") (class "Default")
      (node (ref "ATMEGA32U4-AU") (pin "33") (pinfunction "PE2_33") (pintype "bidirectional"))
    )
    (net (code "119") (name "unconnected-(ATMEGA32U4-AU-PF7-Pad36)") (class "Default")
      (node (ref "ATMEGA32U4-AU") (pin "36") (pinfunction "PF7_36") (pintype "bidirectional"))
    )
    (net (code "120") (name "unconnected-(S1-C-PadK)") (class "Default")
      (node (ref "S1") (pin "K") (pinfunction "C_K") (pintype "passive"))
    )
    (net (code "121") (name "unconnected-(S1-PadA)") (class "Default")
      (node (ref "S1") (pin "A") (pinfunction "A_A") (pintype "passive"))
    )
    (net (code "122") (name "unconnected-(S2-C-PadK)") (class "Default")
      (node (ref "S2") (pin "K") (pinfunction "C_K") (pintype "passive"))
    )
    (net (code "123") (name "unconnected-(S2-PadA)") (class "Default")
      (node (ref "S2") (pin "A") (pinfunction "A_A") (pintype "passive"))
    )
    (net (code "124") (name "unconnected-(S3-C-PadK)") (class "Default")
      (node (ref "S3") (pin "K") (pinfunction "C_K") (pintype "passive"))
    )
    (net (code "125") (name "unconnected-(S3-PadA)") (class "Default")
      (node (ref "S3") (pin "A") (pinfunction "A_A") (pintype "passive"))
    )
    (net (code "126") (name "unconnected-(S4-C-PadK)") (class "Default")
      (node (ref "S4") (pin "K") (pinfunction "C_K") (pintype "passive"))
    )
    (net (code "127") (name "unconnected-(S4-PadA)") (class "Default")
      (node (ref "S4") (pin "A") (pinfunction "A_A") (pintype "passive"))
    )
    (net (code "128") (name "unconnected-(S5-C-PadK)") (class "Default")
      (node (ref "S5") (pin "K") (pinfunction "C_K") (pintype "passive"))
    )
    (net (code "129") (name "unconnected-(S5-PadA)") (class "Default")
      (node (ref "S5") (pin "A") (pinfunction "A_A") (pintype "passive"))
    )
    (net (code "130") (name "unconnected-(S6-C-PadK)") (class "Default")
      (node (ref "S6") (pin "K") (pinfunction "C_K") (pintype "passive"))
    )
    (net (code "131") (name "unconnected-(S6-PadA)") (class "Default")
      (node (ref "S6") (pin "A") (pinfunction "A_A") (pintype "passive"))
    )
    (net (code "132") (name "unconnected-(S7-C-PadK)") (class "Default")
      (node (ref "S7") (pin "K") (pinfunction "C_K") (pintype "passive"))
    )
    (net (code "133") (name "unconnected-(S7-PadA)") (class "Default")
      (node (ref "S7") (pin "A") (pinfunction "A_A") (pintype "passive"))
    )
    (net (code "134") (name "unconnected-(S8-C-PadK)") (class "Default")
      (node (ref "S8") (pin "K") (pinfunction "C_K") (pintype "passive"))
    )
    (net (code "135") (name "unconnected-(S8-PadA)") (class "Default")
      (node (ref "S8") (pin "A") (pinfunction "A_A") (pintype "passive"))
    )
    (net (code "136") (name "unconnected-(S9-C-PadK)") (class "Default")
      (node (ref "S9") (pin "K") (pinfunction "C_K") (pintype "passive"))
    )
    (net (code "137") (name "unconnected-(S9-PadA)") (class "Default")
      (node (ref "S9") (pin "A") (pinfunction "A_A") (pintype "passive"))
    )
    (net (code "138") (name "unconnected-(S10-C-PadK)") (class "Default")
      (node (ref "S10") (pin "K") (pinfunction "C_K") (pintype "passive"))
    )
    (net (code "139") (name "unconnected-(S10-PadA)") (class "Default")
      (node (ref "S10") (pin "A") (pinfunction "A_A") (pintype "passive"))
    )
    (net (code "140") (name "unconnected-(S11-C-PadK)") (class "Default")
      (node (ref "S11") (pin "K") (pinfunction "C_K") (pintype "passive"))
    )
    (net (code "141") (name "unconnected-(S11-PadA)") (class "Default")
      (node (ref "S11") (pin "A") (pinfunction "A_A") (pintype "passive"))
    )
    (net (code "142") (name "unconnected-(S12-C-PadK)") (class "Default")
      (node (ref "S12") (pin "K") (pinfunction "C_K") (pintype "passive"))
    )
    (net (code "143") (name "unconnected-(S12-PadA)") (class "Default")
      (node (ref "S12") (pin "A") (pinfunction "A_A") (pintype "passive"))
    )
    (net (code "144") (name "unconnected-(S13-C-PadK)") (class "Default")
      (node (ref "S13") (pin "K") (pinfunction "C_K") (pintype "passive"))
    )
    (net (code "145") (name "unconnected-(S13-PadA)") (class "Default")
      (node (ref "S13") (pin "A") (pinfunction "A_A") (pintype "passive"))
    )
    (net (code "146") (name "unconnected-(S14-C-PadK)") (class "Default")
      (node (ref "S14") (pin "K") (pinfunction "C_K") (pintype "passive"))
    )
    (net (code "147") (name "unconnected-(S14-PadA)") (class "Default")
      (node (ref "S14") (pin "A") (pinfunction "A_A") (pintype "passive"))
    )
    (net (code "148") (name "unconnected-(S15-C-PadK)") (class "Default")
      (node (ref "S15") (pin "K") (pinfunction "C_K") (pintype "passive"))
    )
    (net (code "149") (name "unconnected-(S15-PadA)") (class "Default")
      (node (ref "S15") (pin "A") (pinfunction "A_A") (pintype "passive"))
    )
    (net (code "150") (name "unconnected-(S16-C-PadK)") (class "Default")
      (node (ref "S16") (pin "K") (pinfunction "C_K") (pintype "passive"))
    )
    (net (code "151") (name "unconnected-(S16-PadA)") (class "Default")
      (node (ref "S16") (pin "A") (pinfunction "A_A") (pintype "passive"))
    )
    (net (code "152") (name "unconnected-(S17-C-PadK)") (class "Default")
      (node (ref "S17") (pin "K") (pinfunction "C_K") (pintype "passive"))
    )
    (net (code "153") (name "unconnected-(S17-PadA)") (class "Default")
      (node (ref "S17") (pin "A") (pinfunction "A_A") (pintype "passive"))
    )
    (net (code "154") (name "unconnected-(S18-C-PadK)") (class "Default")
      (node (ref "S18") (pin "K") (pinfunction "C_K") (pintype "passive"))
    )
    (net (code "155") (name "unconnected-(S18-PadA)") (class "Default")
      (node (ref "S18") (pin "A") (pinfunction "A_A") (pintype "passive"))
    )
    (net (code "156") (name "unconnected-(S19-C-PadK)") (class "Default")
      (node (ref "S19") (pin "K") (pinfunction "C_K") (pintype "passive"))
    )
    (net (code "157") (name "unconnected-(S19-PadA)") (class "Default")
      (node (ref "S19") (pin "A") (pinfunction "A_A") (pintype "passive"))
    )
    (net (code "158") (name "unconnected-(S20-C-PadK)") (class "Default")
      (node (ref "S20") (pin "K") (pinfunction "C_K") (pintype "passive"))
    )
    (net (code "159") (name "unconnected-(S20-PadA)") (class "Default")
      (node (ref "S20") (pin "A") (pinfunction "A_A") (pintype "passive"))
    )
    (net (code "160") (name "unconnected-(S21-C-PadK)") (class "Default")
      (node (ref "S21") (pin "K") (pinfunction "C_K") (pintype "passive"))
    )
    (net (code "161") (name "unconnected-(S21-PadA)") (class "Default")
      (node (ref "S21") (pin "A") (pinfunction "A_A") (pintype "passive"))
    )
    (net (code "162") (name "unconnected-(S22-C-PadK)") (class "Default")
      (node (ref "S22") (pin "K") (pinfunction "C_K") (pintype "passive"))
    )
    (net (code "163") (name "unconnected-(S22-PadA)") (class "Default")
      (node (ref "S22") (pin "A") (pinfunction "A_A") (pintype "passive"))
    )
    (net (code "164") (name "unconnected-(S23-C-PadK)") (class "Default")
      (node (ref "S23") (pin "K") (pinfunction "C_K") (pintype "passive"))
    )
    (net (code "165") (name "unconnected-(S23-PadA)") (class "Default")
      (node (ref "S23") (pin "A") (pinfunction "A_A") (pintype "passive"))
    )
    (net (code "166") (name "unconnected-(S24-C-PadK)") (class "Default")
      (node (ref "S24") (pin "K") (pinfunction "C_K") (pintype "passive"))
    )
    (net (code "167") (name "unconnected-(S24-PadA)") (class "Default")
      (node (ref "S24") (pin "A") (pinfunction "A_A") (pintype "passive"))
    )
    (net (code "168") (name "unconnected-(S25-C-PadK)") (class "Default")
      (node (ref "S25") (pin "K") (pinfunction "C_K") (pintype "passive"))
    )
    (net (code "169") (name "unconnected-(S25-PadA)") (class "Default")
      (node (ref "S25") (pin "A") (pinfunction "A_A") (pintype "passive"))
    )
    (net (code "170") (name "unconnected-(S26-C-PadK)") (class "Default")
      (node (ref "S26") (pin "K") (pinfunction "C_K") (pintype "passive"))
    )
    (net (code "171") (name "unconnected-(S26-PadA)") (class "Default")
      (node (ref "S26") (pin "A") (pinfunction "A_A") (pintype "passive"))
    )
    (net (code "172") (name "unconnected-(S27-C-PadK)") (class "Default")
      (node (ref "S27") (pin "K") (pinfunction "C_K") (pintype "passive"))
    )
    (net (code "173") (name "unconnected-(S27-PadA)") (class "Default")
      (node (ref "S27") (pin "A") (pinfunction "A_A") (pintype "passive"))
    )
    (net (code "174") (name "unconnected-(S28-C-PadK)") (class "Default")
      (node (ref "S28") (pin "K") (pinfunction "C_K") (pintype "passive"))
    )
    (net (code "175") (name "unconnected-(S28-PadA)") (class "Default")
      (node (ref "S28") (pin "A") (pinfunction "A_A") (pintype "passive"))
    )
    (net (code "176") (name "unconnected-(S29-C-PadK)") (class "Default")
      (node (ref "S29") (pin "K") (pinfunction "C_K") (pintype "passive"))
    )
    (net (code "177") (name "unconnected-(S29-PadA)") (class "Default")
      (node (ref "S29") (pin "A") (pinfunction "A_A") (pintype "passive"))
    )
    (net (code "178") (name "unconnected-(S30-C-PadK)") (class "Default")
      (node (ref "S30") (pin "K") (pinfunction "C_K") (pintype "passive"))
    )
    (net (code "179") (name "unconnected-(S30-PadA)") (class "Default")
      (node (ref "S30") (pin "A") (pinfunction "A_A") (pintype "passive"))
    )
    (net (code "180") (name "unconnected-(S31-C-PadK)") (class "Default")
      (node (ref "S31") (pin "K") (pinfunction "C_K") (pintype "passive"))
    )
    (net (code "181") (name "unconnected-(S31-PadA)") (class "Default")
      (node (ref "S31") (pin "A") (pinfunction "A_A") (pintype "passive"))
    )
    (net (code "182") (name "unconnected-(S32-C-PadK)") (class "Default")
      (node (ref "S32") (pin "K") (pinfunction "C_K") (pintype "passive"))
    )
    (net (code "183") (name "unconnected-(S32-PadA)") (class "Default")
      (node (ref "S32") (pin "A") (pinfunction "A_A") (pintype "passive"))
    )
    (net (code "184") (name "unconnected-(S33-C-PadK)") (class "Default")
      (node (ref "S33") (pin "K") (pinfunction "C_K") (pintype "passive"))
    )
    (net (code "185") (name "unconnected-(S33-PadA)") (class "Default")
      (node (ref "S33") (pin "A") (pinfunction "A_A") (pintype "passive"))
    )
    (net (code "186") (name "unconnected-(S34-C-PadK)") (class "Default")
      (node (ref "S34") (pin "K") (pinfunction "C_K") (pintype "passive"))
    )
    (net (code "187") (name "unconnected-(S34-PadA)") (class "Default")
      (node (ref "S34") (pin "A") (pinfunction "A_A") (pintype "passive"))
    )
    (net (code "188") (name "unconnected-(S35-C-PadK)") (class "Default")
      (node (ref "S35") (pin "K") (pinfunction "C_K") (pintype "passive"))
    )
    (net (code "189") (name "unconnected-(S35-PadA)") (class "Default")
      (node (ref "S35") (pin "A") (pinfunction "A_A") (pintype "passive"))
    )
    (net (code "190") (name "unconnected-(S36-C-PadK)") (class "Default")
      (node (ref "S36") (pin "K") (pinfunction "C_K") (pintype "passive"))
    )
    (net (code "191") (name "unconnected-(S36-PadA)") (class "Default")
      (node (ref "S36") (pin "A") (pinfunction "A_A") (pintype "passive"))
    )
    (net (code "192") (name "unconnected-(S37-C-PadK)") (class "Default")
      (node (ref "S37") (pin "K") (pinfunction "C_K") (pintype "passive"))
    )
    (net (code "193") (name "unconnected-(S37-PadA)") (class "Default")
      (node (ref "S37") (pin "A") (pinfunction "A_A") (pintype "passive"))
    )
    (net (code "194") (name "unconnected-(S38-C-PadK)") (class "Default")
      (node (ref "S38") (pin "K") (pinfunction "C_K") (pintype "passive"))
    )
    (net (code "195") (name "unconnected-(S38-PadA)") (class "Default")
      (node (ref "S38") (pin "A") (pinfunction "A_A") (pintype "passive"))
    )
    (net (code "196") (name "unconnected-(S39-C-PadK)") (class "Default")
      (node (ref "S39") (pin "K") (pinfunction "C_K") (pintype "passive"))
    )
    (net (code "197") (name "unconnected-(S39-PadA)") (class "Default")
      (node (ref "S39") (pin "A") (pinfunction "A_A") (pintype "passive"))
    )
    (net (code "198") (name "unconnected-(S40-C-PadK)") (class "Default")
      (node (ref "S40") (pin "K") (pinfunction "C_K") (pintype "passive"))
    )
    (net (code "199") (name "unconnected-(S40-PadA)") (class "Default")
      (node (ref "S40") (pin "A") (pinfunction "A_A") (pintype "passive"))
    )
    (net (code "200") (name "unconnected-(S41-C-PadK)") (class "Default")
      (node (ref "S41") (pin "K") (pinfunction "C_K") (pintype "passive"))
    )
    (net (code "201") (name "unconnected-(S41-PadA)") (class "Default")
      (node (ref "S41") (pin "A") (pinfunction "A_A") (pintype "passive"))
    )
    (net (code "202") (name "unconnected-(S42-C-PadK)") (class "Default")
      (node (ref "S42") (pin "K") (pinfunction "C_K") (pintype "passive"))
    )
    (net (code "203") (name "unconnected-(S42-PadA)") (class "Default")
      (node (ref "S42") (pin "A") (pinfunction "A_A") (pintype "passive"))
    )
    (net (code "204") (name "unconnected-(S43-C-PadK)") (class "Default")
      (node (ref "S43") (pin "K") (pinfunction "C_K") (pintype "passive"))
    )
    (net (code "205") (name "unconnected-(S43-PadA)") (class "Default")
      (node (ref "S43") (pin "A") (pinfunction "A_A") (pintype "passive"))
    )
    (net (code "206") (name "unconnected-(S44-C-PadK)") (class "Default")
      (node (ref "S44") (pin "K") (pinfunction "C_K") (pintype "passive"))
    )
    (net (code "207") (name "unconnected-(S44-PadA)") (class "Default")
      (node (ref "S44") (pin "A") (pinfunction "A_A") (pintype "passive"))
    )
    (net (code "208") (name "unconnected-(S45-C-PadK)") (class "Default")
      (node (ref "S45") (pin "K") (pinfunction "C_K") (pintype "passive"))
    )
    (net (code "209") (name "unconnected-(S45-PadA)") (class "Default")
      (node (ref "S45") (pin "A") (pinfunction "A_A") (pintype "passive"))
    )
    (net (code "210") (name "unconnected-(S46-C-PadK)") (class "Default")
      (node (ref "S46") (pin "K") (pinfunction "C_K") (pintype "passive"))
    )
    (net (code "211") (name "unconnected-(S46-PadA)") (class "Default")
      (node (ref "S46") (pin "A") (pinfunction "A_A") (pintype "passive"))
    )
    (net (code "212") (name "unconnected-(S47-C-PadK)") (class "Default")
      (node (ref "S47") (pin "K") (pinfunction "C_K") (pintype "passive"))
    )
    (net (code "213") (name "unconnected-(S47-PadA)") (class "Default")
      (node (ref "S47") (pin "A") (pinfunction "A_A") (pintype "passive"))
    )
    (net (code "214") (name "unconnected-(S48-C-PadK)") (class "Default")
      (node (ref "S48") (pin "K") (pinfunction "C_K") (pintype "passive"))
    )
    (net (code "215") (name "unconnected-(S48-PadA)") (class "Default")
      (node (ref "S48") (pin "A") (pinfunction "A_A") (pintype "passive"))
    )
    (net (code "216") (name "unconnected-(S49-C-PadK)") (class "Default")
      (node (ref "S49") (pin "K") (pinfunction "C_K") (pintype "passive"))
    )
    (net (code "217") (name "unconnected-(S49-PadA)") (class "Default")
      (node (ref "S49") (pin "A") (pinfunction "A_A") (pintype "passive"))
    )
    (net (code "218") (name "unconnected-(S50-C-PadK)") (class "Default")
      (node (ref "S50") (pin "K") (pinfunction "C_K") (pintype "passive"))
    )
    (net (code "219") (name "unconnected-(S50-PadA)") (class "Default")
      (node (ref "S50") (pin "A") (pinfunction "A_A") (pintype "passive"))
    )
    (net (code "220") (name "unconnected-(S51-C-PadK)") (class "Default")
      (node (ref "S51") (pin "K") (pinfunction "C_K") (pintype "passive"))
    )
    (net (code "221") (name "unconnected-(S51-PadA)") (class "Default")
      (node (ref "S51") (pin "A") (pinfunction "A_A") (pintype "passive"))
    )
    (net (code "222") (name "unconnected-(S52-C-PadK)") (class "Default")
      (node (ref "S52") (pin "K") (pinfunction "C_K") (pintype "passive"))
    )
    (net (code "223") (name "unconnected-(S52-PadA)") (class "Default")
      (node (ref "S52") (pin "A") (pinfunction "A_A") (pintype "passive"))
    )
    (net (code "224") (name "unconnected-(S53-C-PadK)") (class "Default")
      (node (ref "S53") (pin "K") (pinfunction "C_K") (pintype "passive"))
    )
    (net (code "225") (name "unconnected-(S53-PadA)") (class "Default")
      (node (ref "S53") (pin "A") (pinfunction "A_A") (pintype "passive"))
    )
    (net (code "226") (name "unconnected-(S54-C-PadK)") (class "Default")
      (node (ref "S54") (pin "K") (pinfunction "C_K") (pintype "passive"))
    )
    (net (code "227") (name "unconnected-(S54-PadA)") (class "Default")
      (node (ref "S54") (pin "A") (pinfunction "A_A") (pintype "passive"))
    )
    (net (code "228") (name "unconnected-(S55-C-PadK)") (class "Default")
      (node (ref "S55") (pin "K") (pinfunction "C_K") (pintype "passive"))
    )
    (net (code "229") (name "unconnected-(S55-PadA)") (class "Default")
      (node (ref "S55") (pin "A") (pinfunction "A_A") (pintype "passive"))
    )
    (net (code "230") (name "unconnected-(S56-C-PadK)") (class "Default")
      (node (ref "S56") (pin "K") (pinfunction "C_K") (pintype "passive"))
    )
    (net (code "231") (name "unconnected-(S56-PadA)") (class "Default")
      (node (ref "S56") (pin "A") (pinfunction "A_A") (pintype "passive"))
    )
    (net (code "232") (name "unconnected-(S57-C-PadK)") (class "Default")
      (node (ref "S57") (pin "K") (pinfunction "C_K") (pintype "passive"))
    )
    (net (code "233") (name "unconnected-(S57-PadA)") (class "Default")
      (node (ref "S57") (pin "A") (pinfunction "A_A") (pintype "passive"))
    )
    (net (code "234") (name "unconnected-(S58-C-PadK)") (class "Default")
      (node (ref "S58") (pin "K") (pinfunction "C_K") (pintype "passive"))
    )
    (net (code "235") (name "unconnected-(S58-PadA)") (class "Default")
      (node (ref "S58") (pin "A") (pinfunction "A_A") (pintype "passive"))
    )
    (net (code "236") (name "unconnected-(S59-C-PadK)") (class "Default")
      (node (ref "S59") (pin "K") (pinfunction "C_K") (pintype "passive"))
    )
    (net (code "237") (name "unconnected-(S59-PadA)") (class "Default")
      (node (ref "S59") (pin "A") (pinfunction "A_A") (pintype "passive"))
    )
    (net (code "238") (name "unconnected-(S60-C-PadK)") (class "Default")
      (node (ref "S60") (pin "K") (pinfunction "C_K") (pintype "passive"))
    )
    (net (code "239") (name "unconnected-(S60-PadA)") (class "Default")
      (node (ref "S60") (pin "A") (pinfunction "A_A") (pintype "passive"))
    )
    (net (code "240") (name "unconnected-(S61-C-PadK)") (class "Default")
      (node (ref "S61") (pin "K") (pinfunction "C_K") (pintype "passive"))
    )
    (net (code "241") (name "unconnected-(S61-PadA)") (class "Default")
      (node (ref "S61") (pin "A") (pinfunction "A_A") (pintype "passive"))
    )
    (net (code "242") (name "unconnected-(S62-C-PadK)") (class "Default")
      (node (ref "S62") (pin "K") (pinfunction "C_K") (pintype "passive"))
    )
    (net (code "243") (name "unconnected-(S62-PadA)") (class "Default")
      (node (ref "S62") (pin "A") (pinfunction "A_A") (pintype "passive"))
    )
    (net (code "244") (name "unconnected-(S63-C-PadK)") (class "Default")
      (node (ref "S63") (pin "K") (pinfunction "C_K") (pintype "passive"))
    )
    (net (code "245") (name "unconnected-(S63-PadA)") (class "Default")
      (node (ref "S63") (pin "A") (pinfunction "A_A") (pintype "passive"))
    )
    (net (code "246") (name "unconnected-(S64-C-PadK)") (class "Default")
      (node (ref "S64") (pin "K") (pinfunction "C_K") (pintype "passive"))
    )
    (net (code "247") (name "unconnected-(S64-PadA)") (class "Default")
      (node (ref "S64") (pin "A") (pinfunction "A_A") (pintype "passive"))
    )
    (net (code "248") (name "unconnected-(S65-C-PadK)") (class "Default")
      (node (ref "S65") (pin "K") (pinfunction "C_K") (pintype "passive"))
    )
    (net (code "249") (name "unconnected-(S65-PadA)") (class "Default")
      (node (ref "S65") (pin "A") (pinfunction "A_A") (pintype "passive"))
    )
    (net (code "250") (name "unconnected-(S66-C-PadK)") (class "Default")
      (node (ref "S66") (pin "K") (pinfunction "C_K") (pintype "passive"))
    )
    (net (code "251") (name "unconnected-(S66-PadA)") (class "Default")
      (node (ref "S66") (pin "A") (pinfunction "A_A") (pintype "passive"))
    )
    (net (code "252") (name "unconnected-(S67-C-PadK)") (class "Default")
      (node (ref "S67") (pin "K") (pinfunction "C_K") (pintype "passive"))
    )
    (net (code "253") (name "unconnected-(S67-PadA)") (class "Default")
      (node (ref "S67") (pin "A") (pinfunction "A_A") (pintype "passive"))
    )
    (net (code "254") (name "unconnected-(S68-C-PadK)") (class "Default")
      (node (ref "S68") (pin "K") (pinfunction "C_K") (pintype "passive"))
    )
    (net (code "255") (name "unconnected-(S68-PadA)") (class "Default")
      (node (ref "S68") (pin "A") (pinfunction "A_A") (pintype "passive"))
    )
    (net (code "256") (name "unconnected-(S69-C-PadK)") (class "Default")
      (node (ref "S69") (pin "K") (pinfunction "C_K") (pintype "passive"))
    )
    (net (code "257") (name "unconnected-(S69-PadA)") (class "Default")
      (node (ref "S69") (pin "A") (pinfunction "A_A") (pintype "passive"))
    )
    (net (code "258") (name "unconnected-(S70-C-PadK)") (class "Default")
      (node (ref "S70") (pin "K") (pinfunction "C_K") (pintype "passive"))
    )
    (net (code "259") (name "unconnected-(S70-PadA)") (class "Default")
      (node (ref "S70") (pin "A") (pinfunction "A_A") (pintype "passive"))
    )
    (net (code "260") (name "unconnected-(S71-C-PadK)") (class "Default")
      (node (ref "S71") (pin "K") (pinfunction "C_K") (pintype "passive"))
    )
    (net (code "261") (name "unconnected-(S71-PadA)") (class "Default")
      (node (ref "S71") (pin "A") (pinfunction "A_A") (pintype "passive"))
    )
    (net (code "262") (name "unconnected-(S72-C-PadK)") (class "Default")
      (node (ref "S72") (pin "K") (pinfunction "C_K") (pintype "passive"))
    )
    (net (code "263") (name "unconnected-(S72-PadA)") (class "Default")
      (node (ref "S72") (pin "A") (pinfunction "A_A") (pintype "passive"))
    )
    (net (code "264") (name "unconnected-(S73-C-PadK)") (class "Default")
      (node (ref "S73") (pin "K") (pinfunction "C_K") (pintype "passive"))
    )
    (net (code "265") (name "unconnected-(S73-PadA)") (class "Default")
      (node (ref "S73") (pin "A") (pinfunction "A_A") (pintype "passive"))
    )
    (net (code "266") (name "unconnected-(S74-C-PadK)") (class "Default")
      (node (ref "S74") (pin "K") (pinfunction "C_K") (pintype "passive"))
    )
    (net (code "267") (name "unconnected-(S74-PadA)") (class "Default")
      (node (ref "S74") (pin "A") (pinfunction "A_A") (pintype "passive"))
    )
    (net (code "268") (name "unconnected-(S75-C-PadK)") (class "Default")
      (node (ref "S75") (pin "K") (pinfunction "C_K") (pintype "passive"))
    )
    (net (code "269") (name "unconnected-(S75-PadA)") (class "Default")
      (node (ref "S75") (pin "A") (pinfunction "A_A") (pintype "passive"))
    )
    (net (code "270") (name "unconnected-(S76-C-PadK)") (class "Default")
      (node (ref "S76") (pin "K") (pinfunction "C_K") (pintype "passive"))
    )
    (net (code "271") (name "unconnected-(S76-PadA)") (class "Default")
      (node (ref "S76") (pin "A") (pinfunction "A_A") (pintype "passive"))
    )
    (net (code "272") (name "unconnected-(S77-C-PadK)") (class "Default")
      (node (ref "S77") (pin "K") (pinfunction "C_K") (pintype "passive"))
    )
    (net (code "273") (name "unconnected-(S77-PadA)") (class "Default")
      (node (ref "S77") (pin "A") (pinfunction "A_A") (pintype "passive"))
    )
    (net (code "274") (name "unconnected-(S78-C-PadK)") (class "Default")
      (node (ref "S78") (pin "K") (pinfunction "C_K") (pintype "passive"))
    )
    (net (code "275") (name "unconnected-(S78-PadA)") (class "Default")
      (node (ref "S78") (pin "A") (pinfunction "A_A") (pintype "passive"))
    )
    (net (code "276") (name "unconnected-(S79-C-PadK)") (class "Default")
      (node (ref "S79") (pin "K") (pinfunction "C_K") (pintype "passive"))
    )
    (net (code "277") (name "unconnected-(S79-PadA)") (class "Default")
      (node (ref "S79") (pin "A") (pinfunction "A_A") (pintype "passive"))
    )
    (net (code "278") (name "unconnected-(U$1-A8SBU1-PadA8)") (class "Default")
      (node (ref "U$1") (pin "A8") (pinfunction "A8SBU1_A8") (pintype "bidirectional"))
    )
    (net (code "279") (name "unconnected-(U$1-B8SBU2-PadB8)") (class "Default")
      (node (ref "U$1") (pin "B8") (pinfunction "B8SBU2_B8") (pintype "bidirectional"))
    )
  )
)
